# aux-io.net
KiCad netlist of a schematic drawn in EAGLE
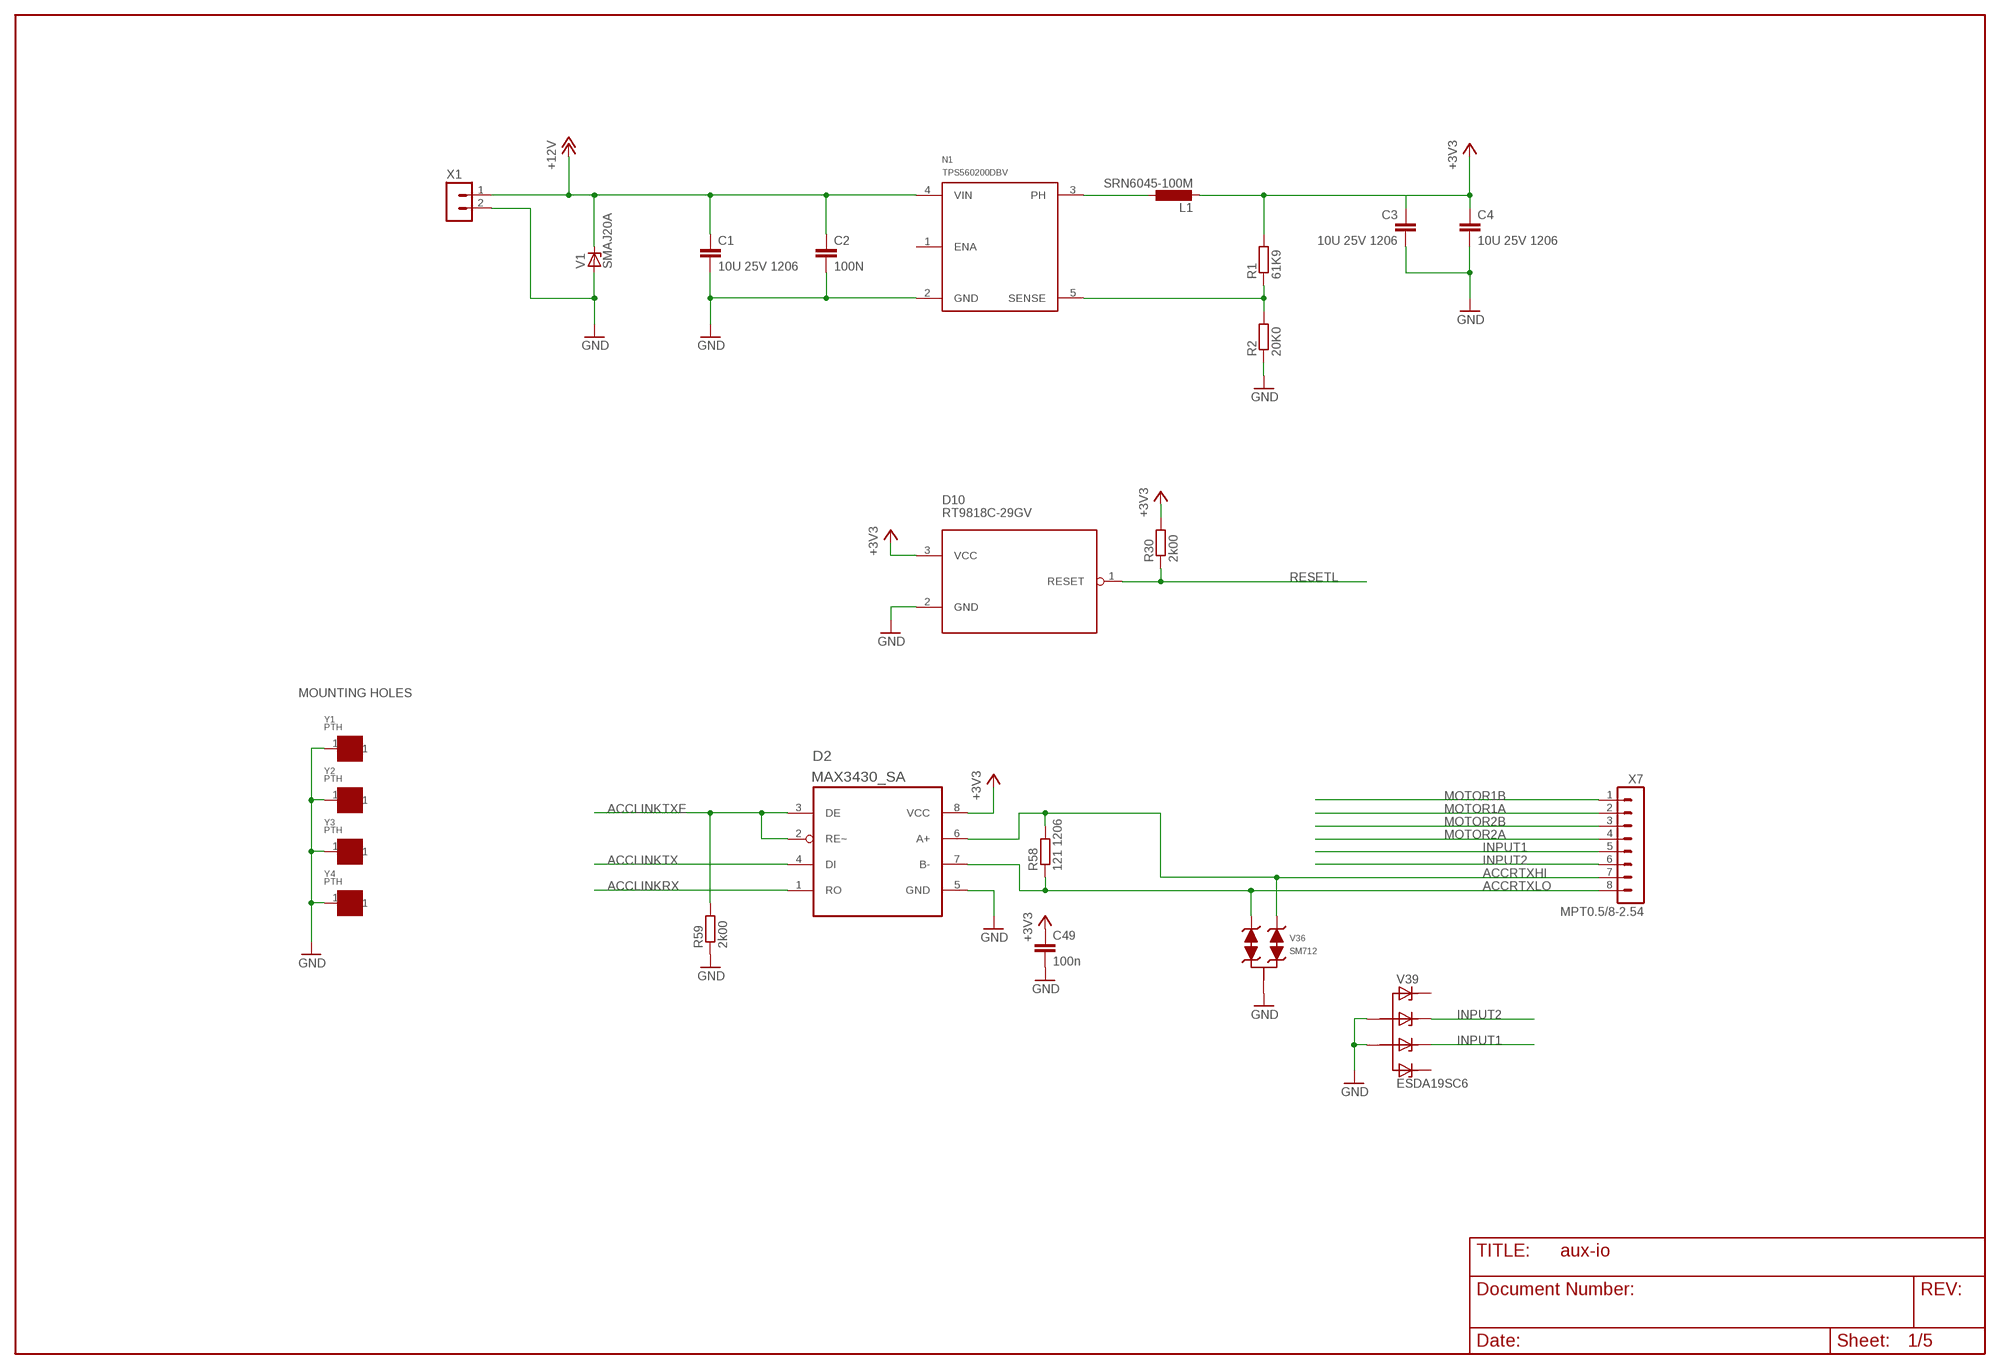
[diagram p0: schematic, sheet 1]
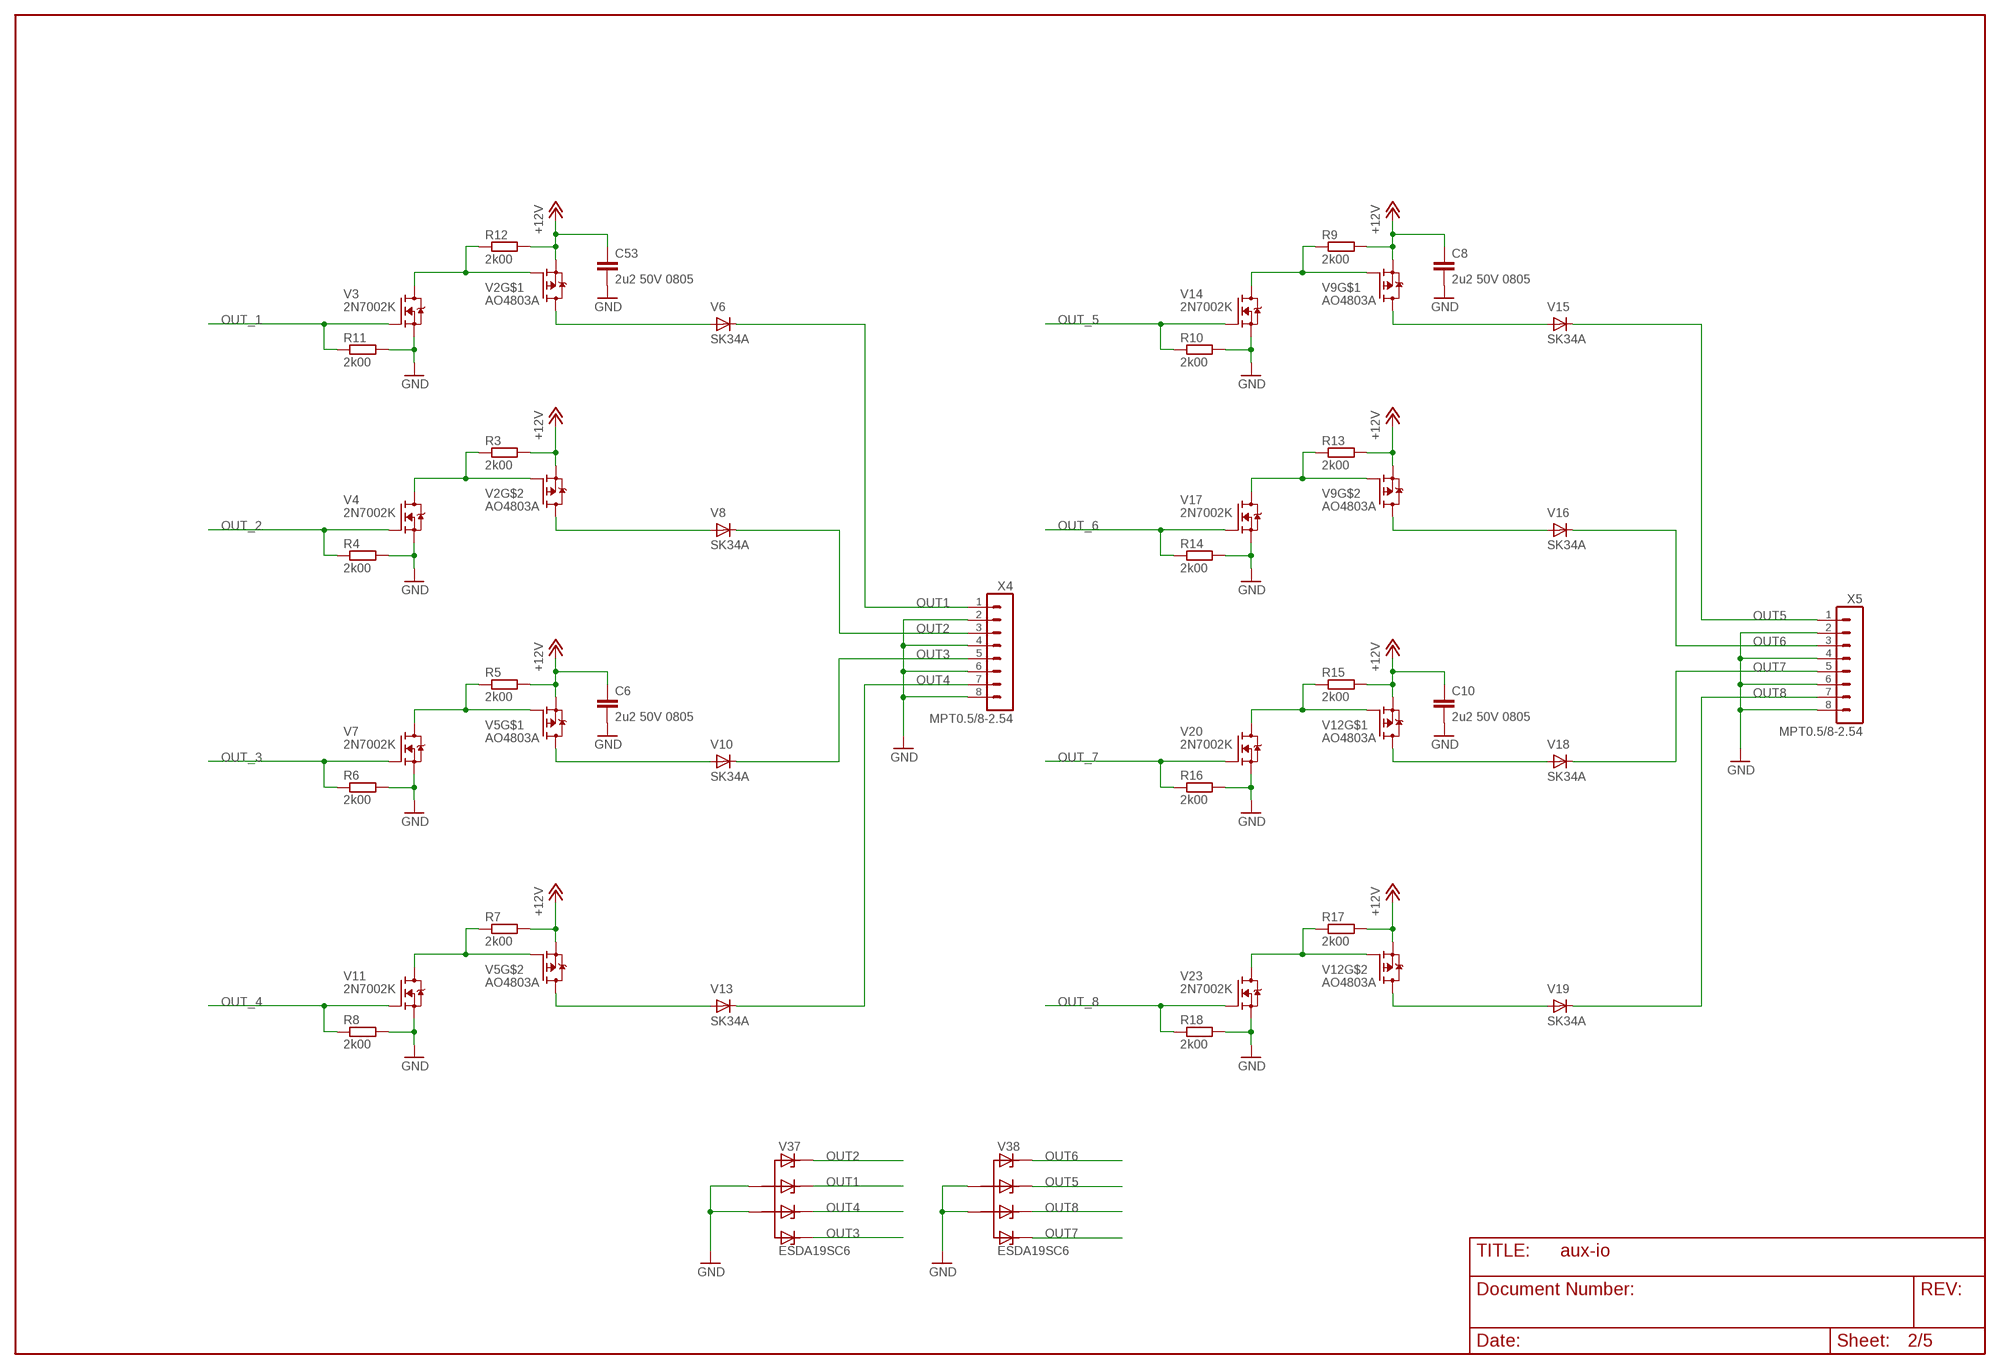
[diagram p1: schematic, sheet 2]
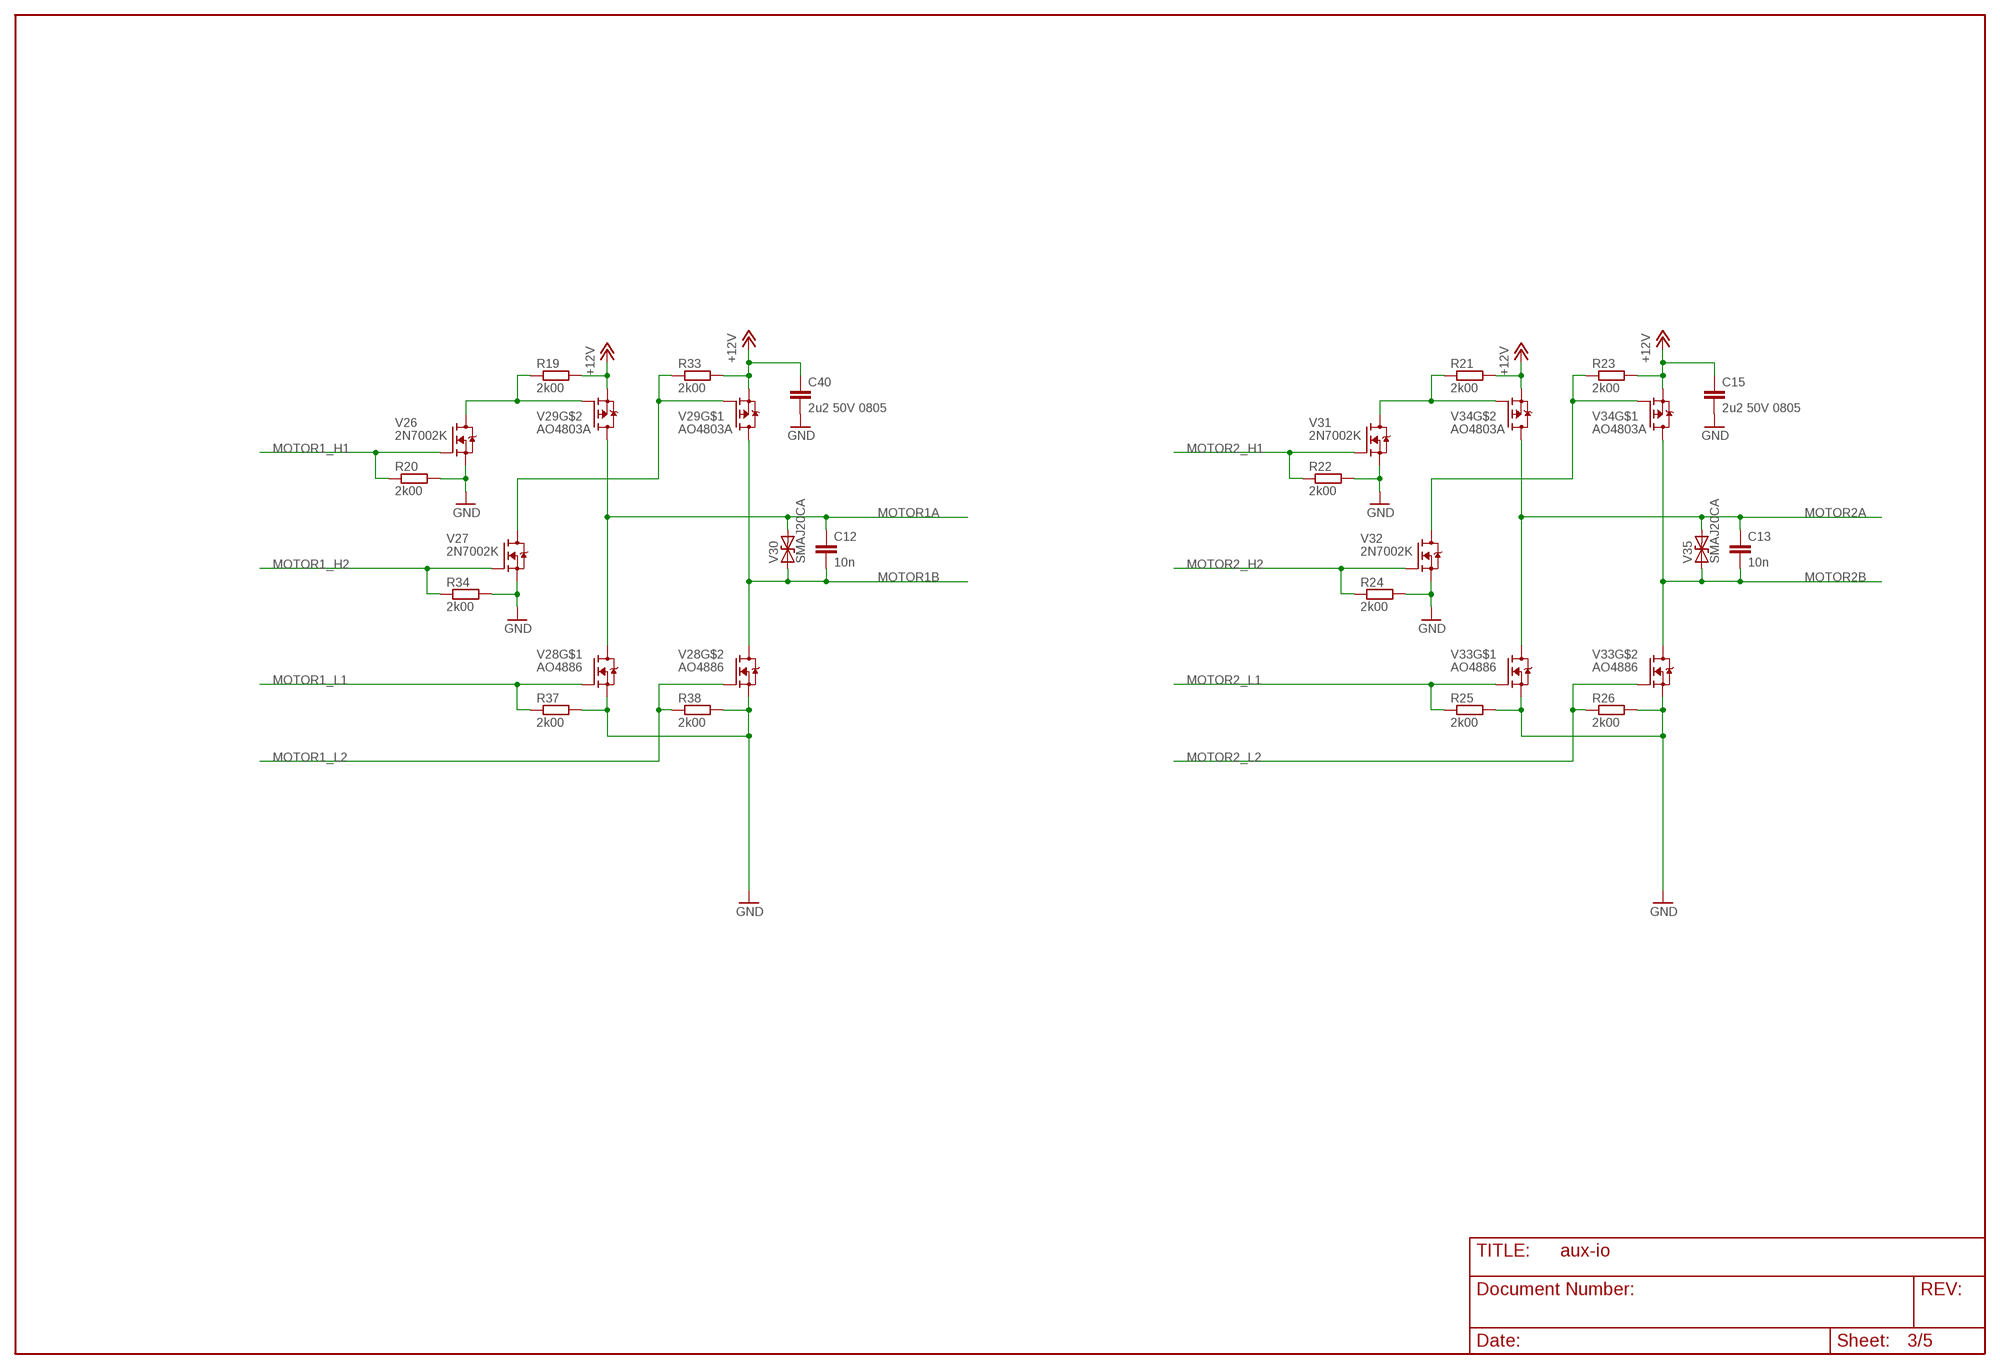
[diagram p2: schematic, sheet 3]
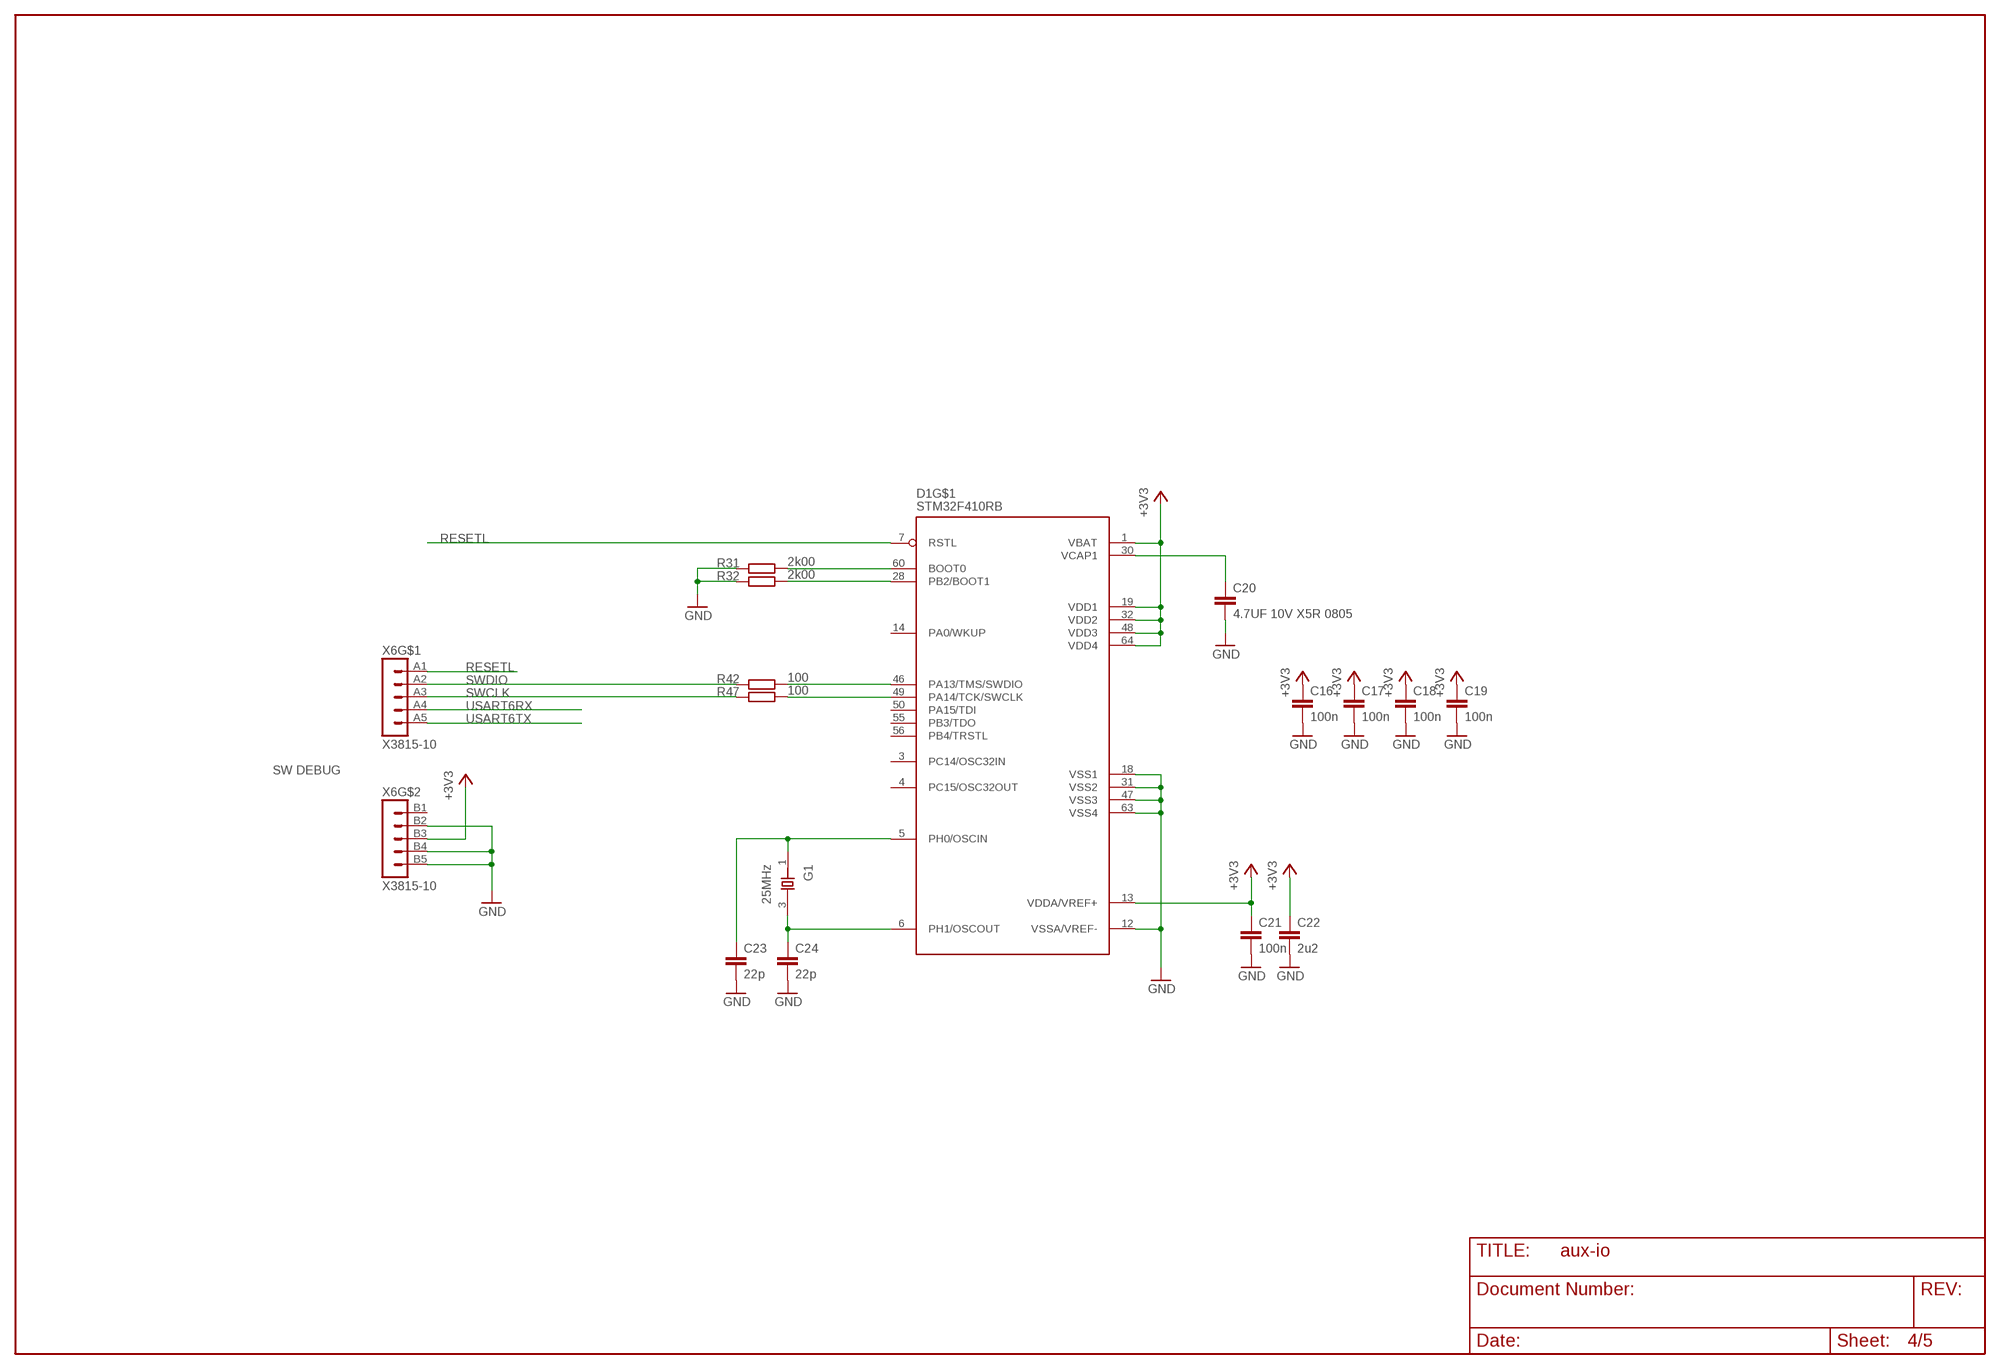
[diagram p3: schematic, sheet 4]
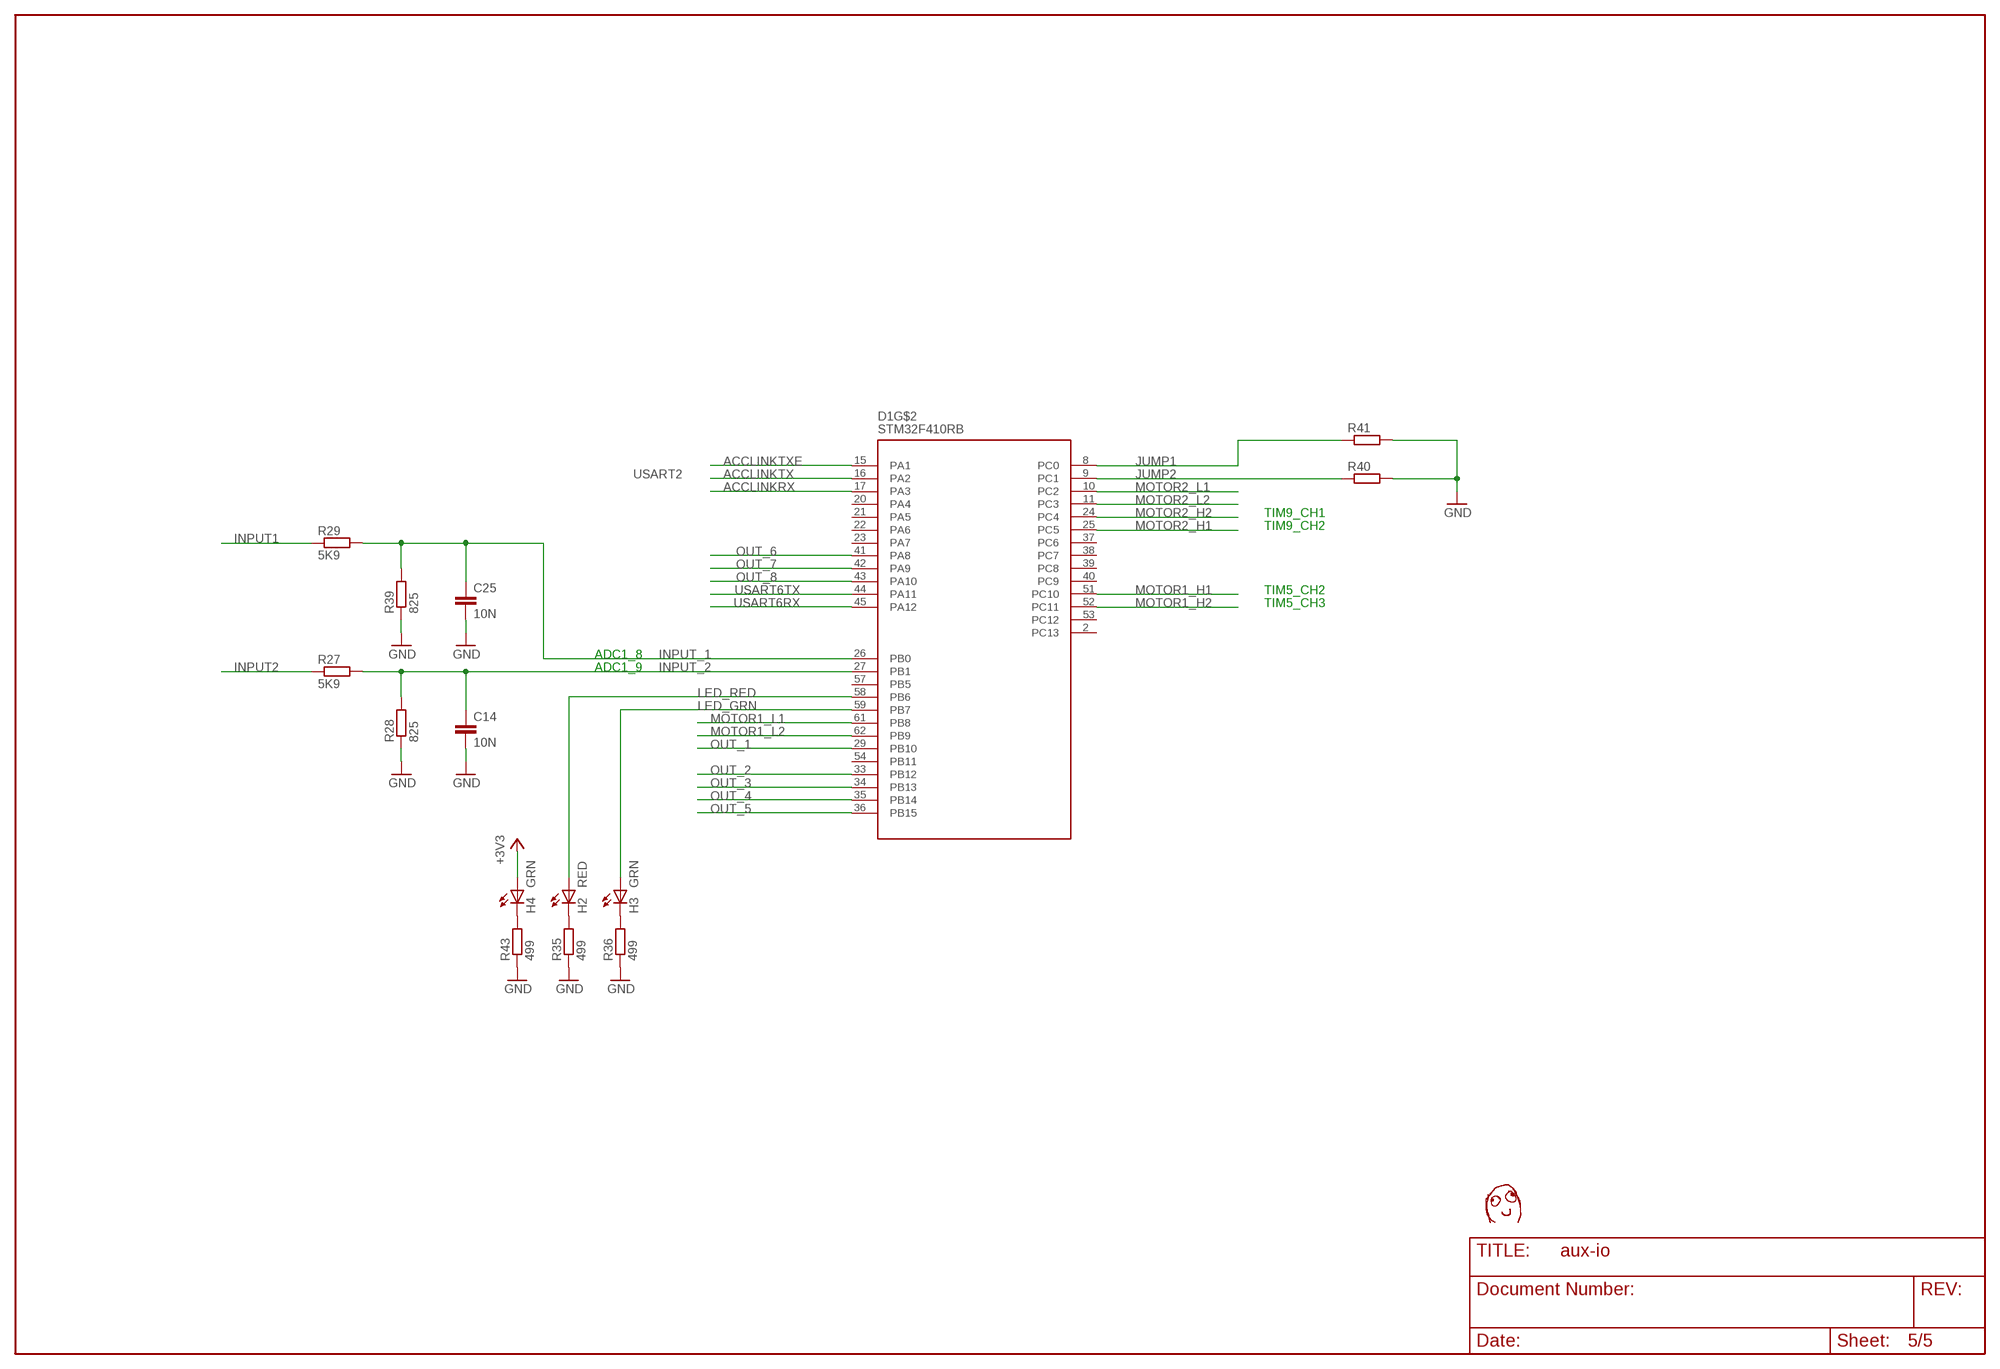
[diagram p4: schematic, sheet 5]

(export (version "E")
  (design (tool "Eeschema 10.0.6"))
  (components
    (comp (ref "C6")
      (value "2u2 50V 0805")
      (footprint "eagle-import:C0805")
      (libsource (lib "eagle-import") (part "CAP0805"))
    )
    (comp (ref "C8")
      (value "2u2 50V 0805")
      (footprint "eagle-import:C0805")
      (libsource (lib "eagle-import") (part "CAP0805"))
    )
    (comp (ref "C10")
      (value "2u2 50V 0805")
      (footprint "eagle-import:C0805")
      (libsource (lib "eagle-import") (part "CAP0805"))
    )
    (comp (ref "C53")
      (value "2u2 50V 0805")
      (footprint "eagle-import:C0805")
      (libsource (lib "eagle-import") (part "CAP0805"))
    )
    (comp (ref "R3")
      (value "2k00")
      (footprint "eagle-import:R0603")
      (libsource (lib "eagle-import") (part "RES0603"))
    )
    (comp (ref "R4")
      (value "2k00")
      (footprint "eagle-import:R0603")
      (libsource (lib "eagle-import") (part "RES0603"))
    )
    (comp (ref "R5")
      (value "2k00")
      (footprint "eagle-import:R0603")
      (libsource (lib "eagle-import") (part "RES0603"))
    )
    (comp (ref "R6")
      (value "2k00")
      (footprint "eagle-import:R0603")
      (libsource (lib "eagle-import") (part "RES0603"))
    )
    (comp (ref "R7")
      (value "2k00")
      (footprint "eagle-import:R0603")
      (libsource (lib "eagle-import") (part "RES0603"))
    )
    (comp (ref "R8")
      (value "2k00")
      (footprint "eagle-import:R0603")
      (libsource (lib "eagle-import") (part "RES0603"))
    )
    (comp (ref "R9")
      (value "2k00")
      (footprint "eagle-import:R0603")
      (libsource (lib "eagle-import") (part "RES0603"))
    )
    (comp (ref "R10")
      (value "2k00")
      (footprint "eagle-import:R0603")
      (libsource (lib "eagle-import") (part "RES0603"))
    )
    (comp (ref "R11")
      (value "2k00")
      (footprint "eagle-import:R0603")
      (libsource (lib "eagle-import") (part "RES0603"))
    )
    (comp (ref "R12")
      (value "2k00")
      (footprint "eagle-import:R0603")
      (libsource (lib "eagle-import") (part "RES0603"))
    )
    (comp (ref "R13")
      (value "2k00")
      (footprint "eagle-import:R0603")
      (libsource (lib "eagle-import") (part "RES0603"))
    )
    (comp (ref "R14")
      (value "2k00")
      (footprint "eagle-import:R0603")
      (libsource (lib "eagle-import") (part "RES0603"))
    )
    (comp (ref "R15")
      (value "2k00")
      (footprint "eagle-import:R0603")
      (libsource (lib "eagle-import") (part "RES0603"))
    )
    (comp (ref "R16")
      (value "2k00")
      (footprint "eagle-import:R0603")
      (libsource (lib "eagle-import") (part "RES0603"))
    )
    (comp (ref "R17")
      (value "2k00")
      (footprint "eagle-import:R0603")
      (libsource (lib "eagle-import") (part "RES0603"))
    )
    (comp (ref "R18")
      (value "2k00")
      (footprint "eagle-import:R0603")
      (libsource (lib "eagle-import") (part "RES0603"))
    )
    (comp (ref "V2")
      (value "AO4803A")
      (footprint "eagle-import:SOIC8-N_MC")
      (libsource (lib "eagle-import") (part "AO4803A"))
    )
    (comp (ref "V3")
      (value "2N7002K")
      (footprint "eagle-import:SOT23")
      (libsource (lib "eagle-import") (part "2N7002K"))
    )
    (comp (ref "V4")
      (value "2N7002K")
      (footprint "eagle-import:SOT23")
      (libsource (lib "eagle-import") (part "2N7002K"))
    )
    (comp (ref "V5")
      (value "AO4803A")
      (footprint "eagle-import:SOIC8-N_MC")
      (libsource (lib "eagle-import") (part "AO4803A"))
    )
    (comp (ref "V6")
      (value "SK34A")
      (footprint "eagle-import:DO214AC")
      (libsource (lib "eagle-import") (part "SK34A"))
    )
    (comp (ref "V7")
      (value "2N7002K")
      (footprint "eagle-import:SOT23")
      (libsource (lib "eagle-import") (part "2N7002K"))
    )
    (comp (ref "V8")
      (value "SK34A")
      (footprint "eagle-import:DO214AC")
      (libsource (lib "eagle-import") (part "SK34A"))
    )
    (comp (ref "V9")
      (value "AO4803A")
      (footprint "eagle-import:SOIC8-N_MC")
      (libsource (lib "eagle-import") (part "AO4803A"))
    )
    (comp (ref "V10")
      (value "SK34A")
      (footprint "eagle-import:DO214AC")
      (libsource (lib "eagle-import") (part "SK34A"))
    )
    (comp (ref "V11")
      (value "2N7002K")
      (footprint "eagle-import:SOT23")
      (libsource (lib "eagle-import") (part "2N7002K"))
    )
    (comp (ref "V12")
      (value "AO4803A")
      (footprint "eagle-import:SOIC8-N_MC")
      (libsource (lib "eagle-import") (part "AO4803A"))
    )
    (comp (ref "V13")
      (value "SK34A")
      (footprint "eagle-import:DO214AC")
      (libsource (lib "eagle-import") (part "SK34A"))
    )
    (comp (ref "V14")
      (value "2N7002K")
      (footprint "eagle-import:SOT23")
      (libsource (lib "eagle-import") (part "2N7002K"))
    )
    (comp (ref "V15")
      (value "SK34A")
      (footprint "eagle-import:DO214AC")
      (libsource (lib "eagle-import") (part "SK34A"))
    )
    (comp (ref "V16")
      (value "SK34A")
      (footprint "eagle-import:DO214AC")
      (libsource (lib "eagle-import") (part "SK34A"))
    )
    (comp (ref "V17")
      (value "2N7002K")
      (footprint "eagle-import:SOT23")
      (libsource (lib "eagle-import") (part "2N7002K"))
    )
    (comp (ref "V18")
      (value "SK34A")
      (footprint "eagle-import:DO214AC")
      (libsource (lib "eagle-import") (part "SK34A"))
    )
    (comp (ref "V19")
      (value "SK34A")
      (footprint "eagle-import:DO214AC")
      (libsource (lib "eagle-import") (part "SK34A"))
    )
    (comp (ref "V20")
      (value "2N7002K")
      (footprint "eagle-import:SOT23")
      (libsource (lib "eagle-import") (part "2N7002K"))
    )
    (comp (ref "V23")
      (value "2N7002K")
      (footprint "eagle-import:SOT23")
      (libsource (lib "eagle-import") (part "2N7002K"))
    )
    (comp (ref "V37")
      (value "ESDA19SC6")
      (footprint "eagle-import:SOT23-6")
      (libsource (lib "eagle-import") (part "ESDAXXSC6"))
    )
    (comp (ref "V38")
      (value "ESDA19SC6")
      (footprint "eagle-import:SOT23-6")
      (libsource (lib "eagle-import") (part "ESDAXXSC6"))
    )
    (comp (ref "X4")
      (value "MPT0.5/8-2.54")
      (footprint "eagle-import:MPT0.5_8-2.54")
      (libsource (lib "eagle-import") (part "MPT0.5/8-2.54"))
    )
    (comp (ref "X5")
      (value "MPT0.5/8-2.54")
      (footprint "eagle-import:MPT0.5_8-2.54")
      (libsource (lib "eagle-import") (part "MPT0.5/8-2.54"))
    )
    (comp (ref "C12")
      (value "10n")
      (footprint "eagle-import:C0603")
      (libsource (lib "eagle-import") (part "CAP0603"))
    )
    (comp (ref "C13")
      (value "10n")
      (footprint "eagle-import:C0603")
      (libsource (lib "eagle-import") (part "CAP0603"))
    )
    (comp (ref "C15")
      (value "2u2 50V 0805")
      (footprint "eagle-import:C0805")
      (libsource (lib "eagle-import") (part "CAP0805"))
    )
    (comp (ref "C40")
      (value "2u2 50V 0805")
      (footprint "eagle-import:C0805")
      (libsource (lib "eagle-import") (part "CAP0805"))
    )
    (comp (ref "R19")
      (value "2k00")
      (footprint "eagle-import:R0603")
      (libsource (lib "eagle-import") (part "RES0603"))
    )
    (comp (ref "R20")
      (value "2k00")
      (footprint "eagle-import:R0603")
      (libsource (lib "eagle-import") (part "RES0603"))
    )
    (comp (ref "R21")
      (value "2k00")
      (footprint "eagle-import:R0603")
      (libsource (lib "eagle-import") (part "RES0603"))
    )
    (comp (ref "R22")
      (value "2k00")
      (footprint "eagle-import:R0603")
      (libsource (lib "eagle-import") (part "RES0603"))
    )
    (comp (ref "R23")
      (value "2k00")
      (footprint "eagle-import:R0603")
      (libsource (lib "eagle-import") (part "RES0603"))
    )
    (comp (ref "R24")
      (value "2k00")
      (footprint "eagle-import:R0603")
      (libsource (lib "eagle-import") (part "RES0603"))
    )
    (comp (ref "R25")
      (value "2k00")
      (footprint "eagle-import:R0603")
      (libsource (lib "eagle-import") (part "RES0603"))
    )
    (comp (ref "R26")
      (value "2k00")
      (footprint "eagle-import:R0603")
      (libsource (lib "eagle-import") (part "RES0603"))
    )
    (comp (ref "R33")
      (value "2k00")
      (footprint "eagle-import:R0603")
      (libsource (lib "eagle-import") (part "RES0603"))
    )
    (comp (ref "R34")
      (value "2k00")
      (footprint "eagle-import:R0603")
      (libsource (lib "eagle-import") (part "RES0603"))
    )
    (comp (ref "R37")
      (value "2k00")
      (footprint "eagle-import:R0603")
      (libsource (lib "eagle-import") (part "RES0603"))
    )
    (comp (ref "R38")
      (value "2k00")
      (footprint "eagle-import:R0603")
      (libsource (lib "eagle-import") (part "RES0603"))
    )
    (comp (ref "V26")
      (value "2N7002K")
      (footprint "eagle-import:SOT23")
      (libsource (lib "eagle-import") (part "2N7002K"))
    )
    (comp (ref "V27")
      (value "2N7002K")
      (footprint "eagle-import:SOT23")
      (libsource (lib "eagle-import") (part "2N7002K"))
    )
    (comp (ref "V28")
      (value "AO4886")
      (footprint "eagle-import:SOIC8-N_MC")
      (libsource (lib "eagle-import") (part "AO4886"))
    )
    (comp (ref "V29")
      (value "AO4803A")
      (footprint "eagle-import:SOIC8-N_MC")
      (libsource (lib "eagle-import") (part "omat_ic_2_AO4803A"))
    )
    (comp (ref "V30")
      (value "SMAJ20CA")
      (footprint "eagle-import:DO214AC")
      (libsource (lib "eagle-import") (part "SMAJXXCA"))
    )
    (comp (ref "V31")
      (value "2N7002K")
      (footprint "eagle-import:SOT23")
      (libsource (lib "eagle-import") (part "2N7002K"))
    )
    (comp (ref "V32")
      (value "2N7002K")
      (footprint "eagle-import:SOT23")
      (libsource (lib "eagle-import") (part "2N7002K"))
    )
    (comp (ref "V33")
      (value "AO4886")
      (footprint "eagle-import:SOIC8-N_MC")
      (libsource (lib "eagle-import") (part "AO4886"))
    )
    (comp (ref "V34")
      (value "AO4803A")
      (footprint "eagle-import:SOIC8-N_MC")
      (libsource (lib "eagle-import") (part "omat_ic_2_AO4803A"))
    )
    (comp (ref "V35")
      (value "SMAJ20CA")
      (footprint "eagle-import:DO214AC")
      (libsource (lib "eagle-import") (part "SMAJXXCA"))
    )
    (comp (ref "C1")
      (value "10U 25V 1206")
      (footprint "eagle-import:C1206")
      (libsource (lib "eagle-import") (part "passiivit_CAP1206"))
    )
    (comp (ref "C2")
      (value "100N")
      (footprint "eagle-import:C0603")
      (libsource (lib "eagle-import") (part "passiivit_CAP0603"))
    )
    (comp (ref "C3")
      (value "10U 25V 1206")
      (footprint "eagle-import:C1206")
      (libsource (lib "eagle-import") (part "passiivit_CAP1206"))
    )
    (comp (ref "C4")
      (value "10U 25V 1206")
      (footprint "eagle-import:C1206")
      (libsource (lib "eagle-import") (part "passiivit_CAP1206"))
    )
    (comp (ref "C49")
      (value "100n")
      (footprint "eagle-import:C0603")
      (libsource (lib "eagle-import") (part "CAP0603"))
    )
    (comp (ref "D2")
      (value "MAX3430_SA")
      (footprint "eagle-import:SOIC8-N_MC")
      (libsource (lib "eagle-import") (part "MAX3088_SA"))
    )
    (comp (ref "D10")
      (value "RT9818C-29GV")
      (footprint "eagle-import:SOT23")
      (libsource (lib "eagle-import") (part "RT9818C-29GV"))
    )
    (comp (ref "L1")
      (value "SRN6045-100M")
      (footprint "eagle-import:SRN6045")
      (libsource (lib "eagle-import") (part "SRN6045-100M"))
    )
    (comp (ref "N1")
      (value "TPS560200DBV")
      (footprint "eagle-import:SOT95P280X145-5N")
      (libsource (lib "eagle-import") (part "TPS560200DBV"))
    )
    (comp (ref "R1")
      (value "61K9")
      (footprint "eagle-import:R0603")
      (libsource (lib "eagle-import") (part "passiivit_RES0603"))
    )
    (comp (ref "R2")
      (value "20K0")
      (footprint "eagle-import:R0603")
      (libsource (lib "eagle-import") (part "passiivit_RES0603"))
    )
    (comp (ref "R30")
      (value "2k00")
      (footprint "eagle-import:R0603")
      (libsource (lib "eagle-import") (part "RES0603"))
    )
    (comp (ref "R58")
      (value "121 1206")
      (footprint "eagle-import:R1206")
      (libsource (lib "eagle-import") (part "RES1206"))
    )
    (comp (ref "R59")
      (value "2k00")
      (footprint "eagle-import:R0603")
      (libsource (lib "eagle-import") (part "RES0603"))
    )
    (comp (ref "V1")
      (value "SMAJ20A")
      (footprint "eagle-import:DO214AC")
      (libsource (lib "eagle-import") (part "SMAJXXA"))
    )
    (comp (ref "V36")
      (value "SM712")
      (footprint "eagle-import:SOT23")
      (libsource (lib "eagle-import") (part "SM712"))
    )
    (comp (ref "V39")
      (value "ESDA19SC6")
      (footprint "eagle-import:SOT23-6")
      (libsource (lib "eagle-import") (part "ESDAXXSC6"))
    )
    (comp (ref "X1")
      (value "TE_RUUVILIITIN2")
      (footprint "eagle-import:TE_RUUVILIITIN2")
      (libsource (lib "eagle-import") (part "TE_RUUVILIITIN2"))
    )
    (comp (ref "X7")
      (value "MPT0.5/8-2.54")
      (footprint "eagle-import:MPT0.5_8-2.54")
      (libsource (lib "eagle-import") (part "MPT0.5/8-2.54"))
    )
    (comp (ref "Y1")
      (value "PTH")
      (footprint "eagle-import:PTH-3.2-6DIA")
      (libsource (lib "eagle-import") (part "PTH"))
    )
    (comp (ref "Y2")
      (value "PTH")
      (footprint "eagle-import:PTH-3.2-6DIA")
      (libsource (lib "eagle-import") (part "PTH"))
    )
    (comp (ref "Y3")
      (value "PTH")
      (footprint "eagle-import:PTH-3.2-6DIA")
      (libsource (lib "eagle-import") (part "PTH"))
    )
    (comp (ref "Y4")
      (value "PTH")
      (footprint "eagle-import:PTH-3.2-6DIA")
      (libsource (lib "eagle-import") (part "PTH"))
    )
    (comp (ref "C16")
      (value "100n")
      (footprint "eagle-import:C0603")
      (libsource (lib "eagle-import") (part "CAP0603"))
    )
    (comp (ref "C17")
      (value "100n")
      (footprint "eagle-import:C0603")
      (libsource (lib "eagle-import") (part "CAP0603"))
    )
    (comp (ref "C18")
      (value "100n")
      (footprint "eagle-import:C0603")
      (libsource (lib "eagle-import") (part "CAP0603"))
    )
    (comp (ref "C19")
      (value "100n")
      (footprint "eagle-import:C0603")
      (libsource (lib "eagle-import") (part "CAP0603"))
    )
    (comp (ref "C20")
      (value "4.7UF 10V X5R 0805")
      (footprint "eagle-import:C0805")
      (libsource (lib "eagle-import") (part "CAP0805"))
    )
    (comp (ref "C21")
      (value "100n")
      (footprint "eagle-import:C0603")
      (libsource (lib "eagle-import") (part "CAP0603"))
    )
    (comp (ref "C22")
      (value "2u2")
      (footprint "eagle-import:C0603")
      (libsource (lib "eagle-import") (part "CAP0603"))
    )
    (comp (ref "C23")
      (value "22p")
      (footprint "eagle-import:C0603")
      (libsource (lib "eagle-import") (part "CAP0603"))
    )
    (comp (ref "C24")
      (value "22p")
      (footprint "eagle-import:C0603")
      (libsource (lib "eagle-import") (part "CAP0603"))
    )
    (comp (ref "D1")
      (value "STM32F410RB")
      (footprint "eagle-import:LQFP-64")
      (libsource (lib "eagle-import") (part "STM32F410RB"))
    )
    (comp (ref "G1")
      (value "25MHz")
      (footprint "eagle-import:X_3225")
      (libsource (lib "eagle-import") (part "XTAL_3225_SMD"))
    )
    (comp (ref "R31")
      (value "2k00")
      (footprint "eagle-import:R0603")
      (libsource (lib "eagle-import") (part "RES0603"))
    )
    (comp (ref "R32")
      (value "2k00")
      (footprint "eagle-import:R0603")
      (libsource (lib "eagle-import") (part "RES0603"))
    )
    (comp (ref "R42")
      (value "100")
      (footprint "eagle-import:R0603")
      (libsource (lib "eagle-import") (part "RES0603"))
    )
    (comp (ref "R47")
      (value "100")
      (footprint "eagle-import:R0603")
      (libsource (lib "eagle-import") (part "RES0603"))
    )
    (comp (ref "X6")
      (value "X3815-10")
      (footprint "eagle-import:15110102601")
      (libsource (lib "eagle-import") (part "X3815-10"))
    )
    (comp (ref "C14")
      (value "10N")
      (footprint "eagle-import:C0603")
      (libsource (lib "eagle-import") (part "passiivit_CAP0603"))
    )
    (comp (ref "C25")
      (value "10N")
      (footprint "eagle-import:C0603")
      (libsource (lib "eagle-import") (part "passiivit_CAP0603"))
    )
    (comp (ref "H2")
      (value "RED")
      (footprint "eagle-import:CHIP-LED0603")
      (libsource (lib "eagle-import") (part "LEDCHIP-LED0603"))
    )
    (comp (ref "H3")
      (value "GRN")
      (footprint "eagle-import:CHIP-LED0603")
      (libsource (lib "eagle-import") (part "LEDCHIP-LED0603"))
    )
    (comp (ref "H4")
      (value "GRN")
      (footprint "eagle-import:CHIP-LED0603")
      (libsource (lib "eagle-import") (part "LEDCHIP-LED0603"))
    )
    (comp (ref "R27")
      (value "5K9")
      (footprint "eagle-import:R1206")
      (libsource (lib "eagle-import") (part "passiivit_RES1206"))
    )
    (comp (ref "R28")
      (value "825")
      (footprint "eagle-import:R0603")
      (libsource (lib "eagle-import") (part "passiivit_RES0603"))
    )
    (comp (ref "R29")
      (value "5K9")
      (footprint "eagle-import:R1206")
      (libsource (lib "eagle-import") (part "passiivit_RES1206"))
    )
    (comp (ref "R35")
      (value "499")
      (footprint "eagle-import:R0603")
      (libsource (lib "eagle-import") (part "RES0603"))
    )
    (comp (ref "R36")
      (value "499")
      (footprint "eagle-import:R0603")
      (libsource (lib "eagle-import") (part "RES0603"))
    )
    (comp (ref "R39")
      (value "825")
      (footprint "eagle-import:R0603")
      (libsource (lib "eagle-import") (part "passiivit_RES0603"))
    )
    (comp (ref "R40")
      (value "RES0603")
      (footprint "eagle-import:R0603")
      (libsource (lib "eagle-import") (part "passiivit_RES0603"))
    )
    (comp (ref "R41")
      (value "RES0603")
      (footprint "eagle-import:R0603")
      (libsource (lib "eagle-import") (part "passiivit_RES0603"))
    )
    (comp (ref "R43")
      (value "499")
      (footprint "eagle-import:R0603")
      (libsource (lib "eagle-import") (part "RES0603"))
    )
    (comp (ref "U$1")
      (value "DAFUG")
      (footprint "eagle-import:DAFUG")
      (libsource (lib "eagle-import") (part "DAFUG"))
    )
  )
  (nets
    (net (code "1") (name "+3V3") (class "Default")
      (node (ref "C16") (pin "1") (pinfunction "1_1") (pintype "passive"))
      (node (ref "C17") (pin "1") (pinfunction "1_1") (pintype "passive"))
      (node (ref "C18") (pin "1") (pinfunction "1_1") (pintype "passive"))
      (node (ref "C19") (pin "1") (pinfunction "1_1") (pintype "passive"))
      (node (ref "C21") (pin "1") (pinfunction "1_1") (pintype "passive"))
      (node (ref "C22") (pin "1") (pinfunction "1_1") (pintype "passive"))
      (node (ref "C3") (pin "1") (pinfunction "1_1") (pintype "passive"))
      (node (ref "C4") (pin "1") (pinfunction "1_1") (pintype "passive"))
      (node (ref "C49") (pin "1") (pinfunction "1_1") (pintype "passive"))
      (node (ref "D1") (pin "1") (pinfunction "VBAT_1") (pintype "bidirectional"))
      (node (ref "D1") (pin "13") (pinfunction "VDDA/VREF+_13") (pintype "bidirectional"))
      (node (ref "D1") (pin "19") (pinfunction "VDD1_19") (pintype "bidirectional"))
      (node (ref "D1") (pin "32") (pinfunction "VDD2_32") (pintype "bidirectional"))
      (node (ref "D1") (pin "48") (pinfunction "VDD3_48") (pintype "bidirectional"))
      (node (ref "D1") (pin "64") (pinfunction "VDD4_64") (pintype "bidirectional"))
      (node (ref "D10") (pin "3") (pinfunction "VCC_3") (pintype "bidirectional"))
      (node (ref "D2") (pin "8") (pinfunction "VCC_8") (pintype "power_in"))
      (node (ref "H4") (pin "A") (pinfunction "A_A") (pintype "passive"))
      (node (ref "L1") (pin "2") (pinfunction "2_2") (pintype "passive"))
      (node (ref "R1") (pin "2") (pinfunction "2_2") (pintype "passive"))
      (node (ref "R30") (pin "2") (pinfunction "2_2") (pintype "passive"))
      (node (ref "X6") (pin "B3") (pinfunction "3_B3") (pintype "passive"))
    )
    (net (code "2") (name "+12V") (class "Default")
      (node (ref "C1") (pin "1") (pinfunction "1_1") (pintype "passive"))
      (node (ref "C10") (pin "1") (pinfunction "1_1") (pintype "passive"))
      (node (ref "C15") (pin "1") (pinfunction "1_1") (pintype "passive"))
      (node (ref "C2") (pin "1") (pinfunction "1_1") (pintype "passive"))
      (node (ref "C40") (pin "1") (pinfunction "1_1") (pintype "passive"))
      (node (ref "C53") (pin "1") (pinfunction "1_1") (pintype "passive"))
      (node (ref "C6") (pin "1") (pinfunction "1_1") (pintype "passive"))
      (node (ref "C8") (pin "1") (pinfunction "1_1") (pintype "passive"))
      (node (ref "N1") (pin "4") (pinfunction "VIN_4") (pintype "bidirectional"))
      (node (ref "R12") (pin "2") (pinfunction "2_2") (pintype "passive"))
      (node (ref "R13") (pin "2") (pinfunction "2_2") (pintype "passive"))
      (node (ref "R15") (pin "2") (pinfunction "2_2") (pintype "passive"))
      (node (ref "R17") (pin "2") (pinfunction "2_2") (pintype "passive"))
      (node (ref "R19") (pin "2") (pinfunction "2_2") (pintype "passive"))
      (node (ref "R21") (pin "2") (pinfunction "2_2") (pintype "passive"))
      (node (ref "R23") (pin "2") (pinfunction "2_2") (pintype "passive"))
      (node (ref "R3") (pin "2") (pinfunction "2_2") (pintype "passive"))
      (node (ref "R33") (pin "2") (pinfunction "2_2") (pintype "passive"))
      (node (ref "R5") (pin "2") (pinfunction "2_2") (pintype "passive"))
      (node (ref "R7") (pin "2") (pinfunction "2_2") (pintype "passive"))
      (node (ref "R9") (pin "2") (pinfunction "2_2") (pintype "passive"))
      (node (ref "V1") (pin "C") (pinfunction "C_C") (pintype "passive"))
      (node (ref "V12") (pin "1") (pinfunction "S_1") (pintype "passive"))
      (node (ref "V12") (pin "3") (pinfunction "S_3") (pintype "passive"))
      (node (ref "V2") (pin "1") (pinfunction "S_1") (pintype "passive"))
      (node (ref "V2") (pin "3") (pinfunction "S_3") (pintype "passive"))
      (node (ref "V29") (pin "1") (pinfunction "S_1") (pintype "passive"))
      (node (ref "V29") (pin "3") (pinfunction "S_3") (pintype "passive"))
      (node (ref "V34") (pin "1") (pinfunction "S_1") (pintype "passive"))
      (node (ref "V34") (pin "3") (pinfunction "S_3") (pintype "passive"))
      (node (ref "V5") (pin "1") (pinfunction "S_1") (pintype "passive"))
      (node (ref "V5") (pin "3") (pinfunction "S_3") (pintype "passive"))
      (node (ref "V9") (pin "1") (pinfunction "S_1") (pintype "passive"))
      (node (ref "V9") (pin "3") (pinfunction "S_3") (pintype "passive"))
      (node (ref "X1") (pin "1") (pinfunction "1_1") (pintype "passive"))
    )
    (net (code "3") (name "ACCLINKRX") (class "Default")
      (node (ref "D1") (pin "17") (pinfunction "PA3_17") (pintype "bidirectional"))
      (node (ref "D2") (pin "1") (pinfunction "RO_1") (pintype "output"))
    )
    (net (code "4") (name "ACCLINKTX") (class "Default")
      (node (ref "D1") (pin "16") (pinfunction "PA2_16") (pintype "bidirectional"))
      (node (ref "D2") (pin "4") (pinfunction "DI_4") (pintype "input"))
    )
    (net (code "5") (name "ACCLINKTXE") (class "Default")
      (node (ref "D1") (pin "15") (pinfunction "PA1_15") (pintype "bidirectional"))
      (node (ref "D2") (pin "2") (pinfunction "RE~{}_2") (pintype "input"))
      (node (ref "D2") (pin "3") (pinfunction "DE_3") (pintype "input"))
      (node (ref "R59") (pin "2") (pinfunction "2_2") (pintype "passive"))
    )
    (net (code "6") (name "ACCRTXHI") (class "Default")
      (node (ref "D2") (pin "6") (pinfunction "A+_6") (pintype "bidirectional"))
      (node (ref "R58") (pin "2") (pinfunction "2_2") (pintype "passive"))
      (node (ref "V36") (pin "1") (pinfunction "1_1") (pintype "bidirectional"))
      (node (ref "X7") (pin "7") (pinfunction "7_7") (pintype "passive"))
    )
    (net (code "7") (name "ACCRTXLO") (class "Default")
      (node (ref "D2") (pin "7") (pinfunction "B-_7") (pintype "bidirectional"))
      (node (ref "R58") (pin "1") (pinfunction "1_1") (pintype "passive"))
      (node (ref "V36") (pin "2") (pinfunction "2_2") (pintype "bidirectional"))
      (node (ref "X7") (pin "8") (pinfunction "8_8") (pintype "passive"))
    )
    (net (code "8") (name "GND") (class "Default")
      (node (ref "C1") (pin "2") (pinfunction "2_2") (pintype "passive"))
      (node (ref "C10") (pin "2") (pinfunction "2_2") (pintype "passive"))
      (node (ref "C14") (pin "2") (pinfunction "2_2") (pintype "passive"))
      (node (ref "C15") (pin "2") (pinfunction "2_2") (pintype "passive"))
      (node (ref "C16") (pin "2") (pinfunction "2_2") (pintype "passive"))
      (node (ref "C17") (pin "2") (pinfunction "2_2") (pintype "passive"))
      (node (ref "C18") (pin "2") (pinfunction "2_2") (pintype "passive"))
      (node (ref "C19") (pin "2") (pinfunction "2_2") (pintype "passive"))
      (node (ref "C2") (pin "2") (pinfunction "2_2") (pintype "passive"))
      (node (ref "C20") (pin "2") (pinfunction "2_2") (pintype "passive"))
      (node (ref "C21") (pin "2") (pinfunction "2_2") (pintype "passive"))
      (node (ref "C22") (pin "2") (pinfunction "2_2") (pintype "passive"))
      (node (ref "C23") (pin "2") (pinfunction "2_2") (pintype "passive"))
      (node (ref "C24") (pin "2") (pinfunction "2_2") (pintype "passive"))
      (node (ref "C25") (pin "2") (pinfunction "2_2") (pintype "passive"))
      (node (ref "C3") (pin "2") (pinfunction "2_2") (pintype "passive"))
      (node (ref "C4") (pin "2") (pinfunction "2_2") (pintype "passive"))
      (node (ref "C40") (pin "2") (pinfunction "2_2") (pintype "passive"))
      (node (ref "C49") (pin "2") (pinfunction "2_2") (pintype "passive"))
      (node (ref "C53") (pin "2") (pinfunction "2_2") (pintype "passive"))
      (node (ref "C6") (pin "2") (pinfunction "2_2") (pintype "passive"))
      (node (ref "C8") (pin "2") (pinfunction "2_2") (pintype "passive"))
      (node (ref "D1") (pin "12") (pinfunction "VSSA/VREF-_12") (pintype "bidirectional"))
      (node (ref "D1") (pin "18") (pinfunction "VSS1_18") (pintype "bidirectional"))
      (node (ref "D1") (pin "31") (pinfunction "VSS2_31") (pintype "bidirectional"))
      (node (ref "D1") (pin "47") (pinfunction "VSS3_47") (pintype "bidirectional"))
      (node (ref "D1") (pin "63") (pinfunction "VSS4_63") (pintype "bidirectional"))
      (node (ref "D10") (pin "2") (pinfunction "GND_2") (pintype "bidirectional"))
      (node (ref "D2") (pin "5") (pinfunction "GND_5") (pintype "power_in"))
      (node (ref "N1") (pin "2") (pinfunction "GND_2") (pintype "bidirectional"))
      (node (ref "R10") (pin "2") (pinfunction "2_2") (pintype "passive"))
      (node (ref "R11") (pin "2") (pinfunction "2_2") (pintype "passive"))
      (node (ref "R14") (pin "2") (pinfunction "2_2") (pintype "passive"))
      (node (ref "R16") (pin "2") (pinfunction "2_2") (pintype "passive"))
      (node (ref "R18") (pin "2") (pinfunction "2_2") (pintype "passive"))
      (node (ref "R2") (pin "1") (pinfunction "1_1") (pintype "passive"))
      (node (ref "R20") (pin "2") (pinfunction "2_2") (pintype "passive"))
      (node (ref "R22") (pin "2") (pinfunction "2_2") (pintype "passive"))
      (node (ref "R24") (pin "2") (pinfunction "2_2") (pintype "passive"))
      (node (ref "R25") (pin "2") (pinfunction "2_2") (pintype "passive"))
      (node (ref "R26") (pin "2") (pinfunction "2_2") (pintype "passive"))
      (node (ref "R28") (pin "1") (pinfunction "1_1") (pintype "passive"))
      (node (ref "R31") (pin "1") (pinfunction "1_1") (pintype "passive"))
      (node (ref "R32") (pin "1") (pinfunction "1_1") (pintype "passive"))
      (node (ref "R34") (pin "2") (pinfunction "2_2") (pintype "passive"))
      (node (ref "R35") (pin "1") (pinfunction "1_1") (pintype "passive"))
      (node (ref "R36") (pin "1") (pinfunction "1_1") (pintype "passive"))
      (node (ref "R37") (pin "2") (pinfunction "2_2") (pintype "passive"))
      (node (ref "R38") (pin "2") (pinfunction "2_2") (pintype "passive"))
      (node (ref "R39") (pin "1") (pinfunction "1_1") (pintype "passive"))
      (node (ref "R4") (pin "2") (pinfunction "2_2") (pintype "passive"))
      (node (ref "R40") (pin "2") (pinfunction "2_2") (pintype "passive"))
      (node (ref "R41") (pin "2") (pinfunction "2_2") (pintype "passive"))
      (node (ref "R43") (pin "1") (pinfunction "1_1") (pintype "passive"))
      (node (ref "R59") (pin "1") (pinfunction "1_1") (pintype "passive"))
      (node (ref "R6") (pin "2") (pinfunction "2_2") (pintype "passive"))
      (node (ref "R8") (pin "2") (pinfunction "2_2") (pintype "passive"))
      (node (ref "V1") (pin "A") (pinfunction "A_A") (pintype "passive"))
      (node (ref "V11") (pin "2") (pinfunction "S_2") (pintype "passive"))
      (node (ref "V14") (pin "2") (pinfunction "S_2") (pintype "passive"))
      (node (ref "V17") (pin "2") (pinfunction "S_2") (pintype "passive"))
      (node (ref "V20") (pin "2") (pinfunction "S_2") (pintype "passive"))
      (node (ref "V23") (pin "2") (pinfunction "S_2") (pintype "passive"))
      (node (ref "V26") (pin "2") (pinfunction "S_2") (pintype "passive"))
      (node (ref "V27") (pin "2") (pinfunction "S_2") (pintype "passive"))
      (node (ref "V28") (pin "1") (pinfunction "S_1") (pintype "passive"))
      (node (ref "V28") (pin "3") (pinfunction "S_3") (pintype "passive"))
      (node (ref "V3") (pin "2") (pinfunction "S_2") (pintype "passive"))
      (node (ref "V31") (pin "2") (pinfunction "S_2") (pintype "passive"))
      (node (ref "V32") (pin "2") (pinfunction "S_2") (pintype "passive"))
      (node (ref "V33") (pin "1") (pinfunction "S_1") (pintype "passive"))
      (node (ref "V33") (pin "3") (pinfunction "S_3") (pintype "passive"))
      (node (ref "V36") (pin "3") (pinfunction "3_3") (pintype "bidirectional"))
      (node (ref "V37") (pin "2") (pinfunction "A_2") (pintype "passive"))
      (node (ref "V37") (pin "5") (pinfunction "A1_5") (pintype "passive"))
      (node (ref "V38") (pin "2") (pinfunction "A_2") (pintype "passive"))
      (node (ref "V38") (pin "5") (pinfunction "A1_5") (pintype "passive"))
      (node (ref "V39") (pin "2") (pinfunction "A_2") (pintype "passive"))
      (node (ref "V39") (pin "5") (pinfunction "A1_5") (pintype "passive"))
      (node (ref "V4") (pin "2") (pinfunction "S_2") (pintype "passive"))
      (node (ref "V7") (pin "2") (pinfunction "S_2") (pintype "passive"))
      (node (ref "X1") (pin "2") (pinfunction "2_2") (pintype "passive"))
      (node (ref "X4") (pin "2") (pinfunction "2_2") (pintype "passive"))
      (node (ref "X4") (pin "4") (pinfunction "4_4") (pintype "passive"))
      (node (ref "X4") (pin "6") (pinfunction "6_6") (pintype "passive"))
      (node (ref "X4") (pin "8") (pinfunction "8_8") (pintype "passive"))
      (node (ref "X5") (pin "2") (pinfunction "2_2") (pintype "passive"))
      (node (ref "X5") (pin "4") (pinfunction "4_4") (pintype "passive"))
      (node (ref "X5") (pin "6") (pinfunction "6_6") (pintype "passive"))
      (node (ref "X5") (pin "8") (pinfunction "8_8") (pintype "passive"))
      (node (ref "X6") (pin "B2") (pinfunction "2_B2") (pintype "passive"))
      (node (ref "X6") (pin "B4") (pinfunction "4_B4") (pintype "passive"))
      (node (ref "X6") (pin "B5") (pinfunction "5_B5") (pintype "passive"))
      (node (ref "Y1") (pin "1") (pinfunction "1_1") (pintype "bidirectional"))
      (node (ref "Y2") (pin "1") (pinfunction "1_1") (pintype "bidirectional"))
      (node (ref "Y3") (pin "1") (pinfunction "1_1") (pintype "bidirectional"))
      (node (ref "Y4") (pin "1") (pinfunction "1_1") (pintype "bidirectional"))
    )
    (net (code "9") (name "INPUT1") (class "Default")
      (node (ref "R29") (pin "1") (pinfunction "1_1") (pintype "passive"))
      (node (ref "V39") (pin "4") (pinfunction "C2_4") (pintype "passive"))
      (node (ref "X7") (pin "5") (pinfunction "5_5") (pintype "passive"))
    )
    (net (code "10") (name "INPUT2") (class "Default")
      (node (ref "R27") (pin "1") (pinfunction "1_1") (pintype "passive"))
      (node (ref "V39") (pin "3") (pinfunction "C1_3") (pintype "passive"))
      (node (ref "X7") (pin "6") (pinfunction "6_6") (pintype "passive"))
    )
    (net (code "11") (name "INPUT_1") (class "Default")
      (node (ref "C25") (pin "1") (pinfunction "1_1") (pintype "passive"))
      (node (ref "D1") (pin "26") (pinfunction "PB0_26") (pintype "bidirectional"))
      (node (ref "R29") (pin "2") (pinfunction "2_2") (pintype "passive"))
      (node (ref "R39") (pin "2") (pinfunction "2_2") (pintype "passive"))
    )
    (net (code "12") (name "INPUT_2") (class "Default")
      (node (ref "C14") (pin "1") (pinfunction "1_1") (pintype "passive"))
      (node (ref "D1") (pin "27") (pinfunction "PB1_27") (pintype "bidirectional"))
      (node (ref "R27") (pin "2") (pinfunction "2_2") (pintype "passive"))
      (node (ref "R28") (pin "2") (pinfunction "2_2") (pintype "passive"))
    )
    (net (code "13") (name "JUMP1") (class "Default")
      (node (ref "D1") (pin "8") (pinfunction "PC0_8") (pintype "bidirectional"))
      (node (ref "R41") (pin "1") (pinfunction "1_1") (pintype "passive"))
    )
    (net (code "14") (name "JUMP2") (class "Default")
      (node (ref "D1") (pin "9") (pinfunction "PC1_9") (pintype "bidirectional"))
      (node (ref "R40") (pin "1") (pinfunction "1_1") (pintype "passive"))
    )
    (net (code "15") (name "LED_GRN") (class "Default")
      (node (ref "D1") (pin "59") (pinfunction "PB7_59") (pintype "bidirectional"))
      (node (ref "H3") (pin "A") (pinfunction "A_A") (pintype "passive"))
    )
    (net (code "16") (name "LED_RED") (class "Default")
      (node (ref "D1") (pin "58") (pinfunction "PB6_58") (pintype "bidirectional"))
      (node (ref "H2") (pin "A") (pinfunction "A_A") (pintype "passive"))
    )
    (net (code "17") (name "MOTOR1A") (class "Default")
      (node (ref "C12") (pin "1") (pinfunction "1_1") (pintype "passive"))
      (node (ref "V28") (pin "5") (pinfunction "D_5") (pintype "passive"))
      (node (ref "V28") (pin "6") (pinfunction "D_6") (pintype "passive"))
      (node (ref "V29") (pin "7") (pinfunction "D_7") (pintype "passive"))
      (node (ref "V29") (pin "8") (pinfunction "D_8") (pintype "passive"))
      (node (ref "V30") (pin "A") (pinfunction "2_A") (pintype "passive"))
      (node (ref "X7") (pin "2") (pinfunction "2_2") (pintype "passive"))
    )
    (net (code "18") (name "MOTOR1B") (class "Default")
      (node (ref "C12") (pin "2") (pinfunction "2_2") (pintype "passive"))
      (node (ref "V28") (pin "7") (pinfunction "D_7") (pintype "passive"))
      (node (ref "V28") (pin "8") (pinfunction "D_8") (pintype "passive"))
      (node (ref "V29") (pin "5") (pinfunction "D_5") (pintype "passive"))
      (node (ref "V29") (pin "6") (pinfunction "D_6") (pintype "passive"))
      (node (ref "V30") (pin "C") (pinfunction "1_C") (pintype "passive"))
      (node (ref "X7") (pin "1") (pinfunction "1_1") (pintype "passive"))
    )
    (net (code "19") (name "MOTOR1_H1") (class "Default")
      (node (ref "D1") (pin "51") (pinfunction "PC10_51") (pintype "bidirectional"))
      (node (ref "R20") (pin "1") (pinfunction "1_1") (pintype "passive"))
      (node (ref "V26") (pin "1") (pinfunction "G_1") (pintype "passive"))
    )
    (net (code "20") (name "MOTOR1_H2") (class "Default")
      (node (ref "D1") (pin "52") (pinfunction "PC11_52") (pintype "bidirectional"))
      (node (ref "R34") (pin "1") (pinfunction "1_1") (pintype "passive"))
      (node (ref "V27") (pin "1") (pinfunction "G_1") (pintype "passive"))
    )
    (net (code "21") (name "MOTOR1_L1") (class "Default")
      (node (ref "D1") (pin "61") (pinfunction "PB8_61") (pintype "bidirectional"))
      (node (ref "R37") (pin "1") (pinfunction "1_1") (pintype "passive"))
      (node (ref "V28") (pin "4") (pinfunction "G_4") (pintype "passive"))
    )
    (net (code "22") (name "MOTOR1_L2") (class "Default")
      (node (ref "D1") (pin "62") (pinfunction "PB9_62") (pintype "bidirectional"))
      (node (ref "R38") (pin "1") (pinfunction "1_1") (pintype "passive"))
      (node (ref "V28") (pin "2") (pinfunction "G_2") (pintype "passive"))
    )
    (net (code "23") (name "MOTOR2A") (class "Default")
      (node (ref "C13") (pin "1") (pinfunction "1_1") (pintype "passive"))
      (node (ref "V33") (pin "5") (pinfunction "D_5") (pintype "passive"))
      (node (ref "V33") (pin "6") (pinfunction "D_6") (pintype "passive"))
      (node (ref "V34") (pin "7") (pinfunction "D_7") (pintype "passive"))
      (node (ref "V34") (pin "8") (pinfunction "D_8") (pintype "passive"))
      (node (ref "V35") (pin "A") (pinfunction "2_A") (pintype "passive"))
      (node (ref "X7") (pin "4") (pinfunction "4_4") (pintype "passive"))
    )
    (net (code "24") (name "MOTOR2B") (class "Default")
      (node (ref "C13") (pin "2") (pinfunction "2_2") (pintype "passive"))
      (node (ref "V33") (pin "7") (pinfunction "D_7") (pintype "passive"))
      (node (ref "V33") (pin "8") (pinfunction "D_8") (pintype "passive"))
      (node (ref "V34") (pin "5") (pinfunction "D_5") (pintype "passive"))
      (node (ref "V34") (pin "6") (pinfunction "D_6") (pintype "passive"))
      (node (ref "V35") (pin "C") (pinfunction "1_C") (pintype "passive"))
      (node (ref "X7") (pin "3") (pinfunction "3_3") (pintype "passive"))
    )
    (net (code "25") (name "MOTOR2_H1") (class "Default")
      (node (ref "D1") (pin "25") (pinfunction "PC5_25") (pintype "bidirectional"))
      (node (ref "R22") (pin "1") (pinfunction "1_1") (pintype "passive"))
      (node (ref "V31") (pin "1") (pinfunction "G_1") (pintype "passive"))
    )
    (net (code "26") (name "MOTOR2_H2") (class "Default")
      (node (ref "D1") (pin "24") (pinfunction "PC4_24") (pintype "bidirectional"))
      (node (ref "R24") (pin "1") (pinfunction "1_1") (pintype "passive"))
      (node (ref "V32") (pin "1") (pinfunction "G_1") (pintype "passive"))
    )
    (net (code "27") (name "MOTOR2_L1") (class "Default")
      (node (ref "D1") (pin "10") (pinfunction "PC2_10") (pintype "bidirectional"))
      (node (ref "R25") (pin "1") (pinfunction "1_1") (pintype "passive"))
      (node (ref "V33") (pin "4") (pinfunction "G_4") (pintype "passive"))
    )
    (net (code "28") (name "MOTOR2_L2") (class "Default")
      (node (ref "D1") (pin "11") (pinfunction "PC3_11") (pintype "bidirectional"))
      (node (ref "R26") (pin "1") (pinfunction "1_1") (pintype "passive"))
      (node (ref "V33") (pin "2") (pinfunction "G_2") (pintype "passive"))
    )
    (net (code "29") (name "Net-(D1A-BOOT0)") (class "Default")
      (node (ref "D1") (pin "60") (pinfunction "BOOT0_60") (pintype "bidirectional"))
      (node (ref "R31") (pin "2") (pinfunction "2_2") (pintype "passive"))
    )
    (net (code "30") (name "Net-(D1A-PA13{slash}TMS{slash}SWDIO)") (class "Default")
      (node (ref "D1") (pin "46") (pinfunction "PA13/TMS/SWDIO_46") (pintype "bidirectional"))
      (node (ref "R42") (pin "2") (pinfunction "2_2") (pintype "passive"))
    )
    (net (code "31") (name "Net-(D1A-PA14{slash}TCK{slash}SWCLK)") (class "Default")
      (node (ref "D1") (pin "49") (pinfunction "PA14/TCK/SWCLK_49") (pintype "bidirectional"))
      (node (ref "R47") (pin "2") (pinfunction "2_2") (pintype "passive"))
    )
    (net (code "32") (name "Net-(D1A-PB2{slash}BOOT1)") (class "Default")
      (node (ref "D1") (pin "28") (pinfunction "PB2/BOOT1_28") (pintype "bidirectional"))
      (node (ref "R32") (pin "2") (pinfunction "2_2") (pintype "passive"))
    )
    (net (code "33") (name "Net-(D1A-PH0{slash}OSCIN)") (class "Default")
      (node (ref "C23") (pin "1") (pinfunction "1_1") (pintype "passive"))
      (node (ref "D1") (pin "5") (pinfunction "PH0/OSCIN_5") (pintype "bidirectional"))
      (node (ref "G1") (pin "1") (pinfunction "X1_1") (pintype "bidirectional"))
    )
    (net (code "34") (name "Net-(D1A-PH1{slash}OSCOUT)") (class "Default")
      (node (ref "C24") (pin "1") (pinfunction "1_1") (pintype "passive"))
      (node (ref "D1") (pin "6") (pinfunction "PH1/OSCOUT_6") (pintype "bidirectional"))
      (node (ref "G1") (pin "3") (pinfunction "X2_3") (pintype "bidirectional"))
    )
    (net (code "35") (name "Net-(D1A-VCAP1)") (class "Default")
      (node (ref "C20") (pin "1") (pinfunction "1_1") (pintype "passive"))
      (node (ref "D1") (pin "30") (pinfunction "VCAP1_30") (pintype "bidirectional"))
    )
    (net (code "36") (name "Net-(H2-PadC)") (class "Default")
      (node (ref "H2") (pin "C") (pinfunction "C_C") (pintype "passive"))
      (node (ref "R35") (pin "2") (pinfunction "2_2") (pintype "passive"))
    )
    (net (code "37") (name "Net-(H3-PadC)") (class "Default")
      (node (ref "H3") (pin "C") (pinfunction "C_C") (pintype "passive"))
      (node (ref "R36") (pin "2") (pinfunction "2_2") (pintype "passive"))
    )
    (net (code "38") (name "Net-(H4-PadC)") (class "Default")
      (node (ref "H4") (pin "C") (pinfunction "C_C") (pintype "passive"))
      (node (ref "R43") (pin "2") (pinfunction "2_2") (pintype "passive"))
    )
    (net (code "39") (name "Net-(N1-PH)") (class "Default")
      (node (ref "L1") (pin "1") (pinfunction "1_1") (pintype "passive"))
      (node (ref "N1") (pin "3") (pinfunction "PH_3") (pintype "bidirectional"))
    )
    (net (code "40") (name "Net-(N1-SENSE)") (class "Default")
      (node (ref "N1") (pin "5") (pinfunction "SENSE_5") (pintype "bidirectional"))
      (node (ref "R1") (pin "1") (pinfunction "1_1") (pintype "passive"))
      (node (ref "R2") (pin "2") (pinfunction "2_2") (pintype "passive"))
    )
    (net (code "41") (name "Net-(V2A-D-Pad5)") (class "Default")
      (node (ref "V2") (pin "5") (pinfunction "D_5") (pintype "passive"))
      (node (ref "V2") (pin "6") (pinfunction "D_6") (pintype "passive"))
      (node (ref "V6") (pin "A") (pinfunction "A_A") (pintype "passive"))
    )
    (net (code "42") (name "Net-(V2A-G)") (class "Default")
      (node (ref "R12") (pin "1") (pinfunction "1_1") (pintype "passive"))
      (node (ref "V2") (pin "4") (pinfunction "G_4") (pintype "passive"))
      (node (ref "V3") (pin "3") (pinfunction "D_3") (pintype "passive"))
    )
    (net (code "43") (name "Net-(V2B-D-Pad7)") (class "Default")
      (node (ref "V2") (pin "7") (pinfunction "D_7") (pintype "passive"))
      (node (ref "V2") (pin "8") (pinfunction "D_8") (pintype "passive"))
      (node (ref "V8") (pin "A") (pinfunction "A_A") (pintype "passive"))
    )
    (net (code "44") (name "Net-(V2B-G)") (class "Default")
      (node (ref "R3") (pin "1") (pinfunction "1_1") (pintype "passive"))
      (node (ref "V2") (pin "2") (pinfunction "G_2") (pintype "passive"))
      (node (ref "V4") (pin "3") (pinfunction "D_3") (pintype "passive"))
    )
    (net (code "45") (name "Net-(V5A-G)") (class "Default")
      (node (ref "R5") (pin "1") (pinfunction "1_1") (pintype "passive"))
      (node (ref "V5") (pin "4") (pinfunction "G_4") (pintype "passive"))
      (node (ref "V7") (pin "3") (pinfunction "D_3") (pintype "passive"))
    )
    (net (code "46") (name "Net-(V10-PadA)") (class "Default")
      (node (ref "V10") (pin "A") (pinfunction "A_A") (pintype "passive"))
      (node (ref "V5") (pin "5") (pinfunction "D_5") (pintype "passive"))
      (node (ref "V5") (pin "6") (pinfunction "D_6") (pintype "passive"))
    )
    (net (code "47") (name "Net-(V11-D)") (class "Default")
      (node (ref "R7") (pin "1") (pinfunction "1_1") (pintype "passive"))
      (node (ref "V11") (pin "3") (pinfunction "D_3") (pintype "passive"))
      (node (ref "V5") (pin "2") (pinfunction "G_2") (pintype "passive"))
    )
    (net (code "48") (name "Net-(V12A-D-Pad5)") (class "Default")
      (node (ref "V12") (pin "5") (pinfunction "D_5") (pintype "passive"))
      (node (ref "V12") (pin "6") (pinfunction "D_6") (pintype "passive"))
      (node (ref "V18") (pin "A") (pinfunction "A_A") (pintype "passive"))
    )
    (net (code "49") (name "Net-(V12A-G)") (class "Default")
      (node (ref "R15") (pin "1") (pinfunction "1_1") (pintype "passive"))
      (node (ref "V12") (pin "4") (pinfunction "G_4") (pintype "passive"))
      (node (ref "V20") (pin "3") (pinfunction "D_3") (pintype "passive"))
    )
    (net (code "50") (name "Net-(V12B-D-Pad7)") (class "Default")
      (node (ref "V12") (pin "7") (pinfunction "D_7") (pintype "passive"))
      (node (ref "V12") (pin "8") (pinfunction "D_8") (pintype "passive"))
      (node (ref "V19") (pin "A") (pinfunction "A_A") (pintype "passive"))
    )
    (net (code "51") (name "Net-(V12B-G)") (class "Default")
      (node (ref "R17") (pin "1") (pinfunction "1_1") (pintype "passive"))
      (node (ref "V12") (pin "2") (pinfunction "G_2") (pintype "passive"))
      (node (ref "V23") (pin "3") (pinfunction "D_3") (pintype "passive"))
    )
    (net (code "52") (name "Net-(V13-PadA)") (class "Default")
      (node (ref "V13") (pin "A") (pinfunction "A_A") (pintype "passive"))
      (node (ref "V5") (pin "7") (pinfunction "D_7") (pintype "passive"))
      (node (ref "V5") (pin "8") (pinfunction "D_8") (pintype "passive"))
    )
    (net (code "53") (name "Net-(V14-D)") (class "Default")
      (node (ref "R9") (pin "1") (pinfunction "1_1") (pintype "passive"))
      (node (ref "V14") (pin "3") (pinfunction "D_3") (pintype "passive"))
      (node (ref "V9") (pin "4") (pinfunction "G_4") (pintype "passive"))
    )
    (net (code "54") (name "Net-(V15-PadA)") (class "Default")
      (node (ref "V15") (pin "A") (pinfunction "A_A") (pintype "passive"))
      (node (ref "V9") (pin "5") (pinfunction "D_5") (pintype "passive"))
      (node (ref "V9") (pin "6") (pinfunction "D_6") (pintype "passive"))
    )
    (net (code "55") (name "Net-(V16-PadA)") (class "Default")
      (node (ref "V16") (pin "A") (pinfunction "A_A") (pintype "passive"))
      (node (ref "V9") (pin "7") (pinfunction "D_7") (pintype "passive"))
      (node (ref "V9") (pin "8") (pinfunction "D_8") (pintype "passive"))
    )
    (net (code "56") (name "Net-(V17-D)") (class "Default")
      (node (ref "R13") (pin "1") (pinfunction "1_1") (pintype "passive"))
      (node (ref "V17") (pin "3") (pinfunction "D_3") (pintype "passive"))
      (node (ref "V9") (pin "2") (pinfunction "G_2") (pintype "passive"))
    )
    (net (code "57") (name "Net-(V26-D)") (class "Default")
      (node (ref "R19") (pin "1") (pinfunction "1_1") (pintype "passive"))
      (node (ref "V26") (pin "3") (pinfunction "D_3") (pintype "passive"))
      (node (ref "V29") (pin "2") (pinfunction "G_2") (pintype "passive"))
    )
    (net (code "58") (name "Net-(V27-D)") (class "Default")
      (node (ref "R33") (pin "1") (pinfunction "1_1") (pintype "passive"))
      (node (ref "V27") (pin "3") (pinfunction "D_3") (pintype "passive"))
      (node (ref "V29") (pin "4") (pinfunction "G_4") (pintype "passive"))
    )
    (net (code "59") (name "Net-(V31-D)") (class "Default")
      (node (ref "R21") (pin "1") (pinfunction "1_1") (pintype "passive"))
      (node (ref "V31") (pin "3") (pinfunction "D_3") (pintype "passive"))
      (node (ref "V34") (pin "2") (pinfunction "G_2") (pintype "passive"))
    )
    (net (code "60") (name "Net-(V32-D)") (class "Default")
      (node (ref "R23") (pin "1") (pinfunction "1_1") (pintype "passive"))
      (node (ref "V32") (pin "3") (pinfunction "D_3") (pintype "passive"))
      (node (ref "V34") (pin "4") (pinfunction "G_4") (pintype "passive"))
    )
    (net (code "61") (name "OUT1") (class "Default")
      (node (ref "V37") (pin "3") (pinfunction "C1_3") (pintype "passive"))
      (node (ref "V6") (pin "C") (pinfunction "C_C") (pintype "passive"))
      (node (ref "X4") (pin "1") (pinfunction "1_1") (pintype "passive"))
    )
    (net (code "62") (name "OUT2") (class "Default")
      (node (ref "V37") (pin "1") (pinfunction "C_1") (pintype "passive"))
      (node (ref "V8") (pin "C") (pinfunction "C_C") (pintype "passive"))
      (node (ref "X4") (pin "3") (pinfunction "3_3") (pintype "passive"))
    )
    (net (code "63") (name "OUT3") (class "Default")
      (node (ref "V10") (pin "C") (pinfunction "C_C") (pintype "passive"))
      (node (ref "V37") (pin "6") (pinfunction "C3_6") (pintype "passive"))
      (node (ref "X4") (pin "5") (pinfunction "5_5") (pintype "passive"))
    )
    (net (code "64") (name "OUT4") (class "Default")
      (node (ref "V13") (pin "C") (pinfunction "C_C") (pintype "passive"))
      (node (ref "V37") (pin "4") (pinfunction "C2_4") (pintype "passive"))
      (node (ref "X4") (pin "7") (pinfunction "7_7") (pintype "passive"))
    )
    (net (code "65") (name "OUT5") (class "Default")
      (node (ref "V15") (pin "C") (pinfunction "C_C") (pintype "passive"))
      (node (ref "V38") (pin "3") (pinfunction "C1_3") (pintype "passive"))
      (node (ref "X5") (pin "1") (pinfunction "1_1") (pintype "passive"))
    )
    (net (code "66") (name "OUT6") (class "Default")
      (node (ref "V16") (pin "C") (pinfunction "C_C") (pintype "passive"))
      (node (ref "V38") (pin "1") (pinfunction "C_1") (pintype "passive"))
      (node (ref "X5") (pin "3") (pinfunction "3_3") (pintype "passive"))
    )
    (net (code "67") (name "OUT7") (class "Default")
      (node (ref "V18") (pin "C") (pinfunction "C_C") (pintype "passive"))
      (node (ref "V38") (pin "6") (pinfunction "C3_6") (pintype "passive"))
      (node (ref "X5") (pin "5") (pinfunction "5_5") (pintype "passive"))
    )
    (net (code "68") (name "OUT8") (class "Default")
      (node (ref "V19") (pin "C") (pinfunction "C_C") (pintype "passive"))
      (node (ref "V38") (pin "4") (pinfunction "C2_4") (pintype "passive"))
      (node (ref "X5") (pin "7") (pinfunction "7_7") (pintype "passive"))
    )
    (net (code "69") (name "OUT_1") (class "Default")
      (node (ref "D1") (pin "29") (pinfunction "PB10_29") (pintype "bidirectional"))
      (node (ref "R11") (pin "1") (pinfunction "1_1") (pintype "passive"))
      (node (ref "V3") (pin "1") (pinfunction "G_1") (pintype "passive"))
    )
    (net (code "70") (name "OUT_2") (class "Default")
      (node (ref "D1") (pin "33") (pinfunction "PB12_33") (pintype "bidirectional"))
      (node (ref "R4") (pin "1") (pinfunction "1_1") (pintype "passive"))
      (node (ref "V4") (pin "1") (pinfunction "G_1") (pintype "passive"))
    )
    (net (code "71") (name "OUT_3") (class "Default")
      (node (ref "D1") (pin "34") (pinfunction "PB13_34") (pintype "bidirectional"))
      (node (ref "R6") (pin "1") (pinfunction "1_1") (pintype "passive"))
      (node (ref "V7") (pin "1") (pinfunction "G_1") (pintype "passive"))
    )
    (net (code "72") (name "OUT_4") (class "Default")
      (node (ref "D1") (pin "35") (pinfunction "PB14_35") (pintype "bidirectional"))
      (node (ref "R8") (pin "1") (pinfunction "1_1") (pintype "passive"))
      (node (ref "V11") (pin "1") (pinfunction "G_1") (pintype "passive"))
    )
    (net (code "73") (name "OUT_5") (class "Default")
      (node (ref "D1") (pin "36") (pinfunction "PB15_36") (pintype "bidirectional"))
      (node (ref "R10") (pin "1") (pinfunction "1_1") (pintype "passive"))
      (node (ref "V14") (pin "1") (pinfunction "G_1") (pintype "passive"))
    )
    (net (code "74") (name "OUT_6") (class "Default")
      (node (ref "D1") (pin "41") (pinfunction "PA8_41") (pintype "bidirectional"))
      (node (ref "R14") (pin "1") (pinfunction "1_1") (pintype "passive"))
      (node (ref "V17") (pin "1") (pinfunction "G_1") (pintype "passive"))
    )
    (net (code "75") (name "OUT_7") (class "Default")
      (node (ref "D1") (pin "42") (pinfunction "PA9_42") (pintype "bidirectional"))
      (node (ref "R16") (pin "1") (pinfunction "1_1") (pintype "passive"))
      (node (ref "V20") (pin "1") (pinfunction "G_1") (pintype "passive"))
    )
    (net (code "76") (name "OUT_8") (class "Default")
      (node (ref "D1") (pin "43") (pinfunction "PA10_43") (pintype "bidirectional"))
      (node (ref "R18") (pin "1") (pinfunction "1_1") (pintype "passive"))
      (node (ref "V23") (pin "1") (pinfunction "G_1") (pintype "passive"))
    )
    (net (code "77") (name "RESETL") (class "Default")
      (node (ref "D1") (pin "7") (pinfunction "RSTL_7") (pintype "bidirectional"))
      (node (ref "D10") (pin "1") (pinfunction "RESET_1") (pintype "bidirectional"))
      (node (ref "R30") (pin "1") (pinfunction "1_1") (pintype "passive"))
      (node (ref "X6") (pin "A1") (pinfunction "1_A1") (pintype "passive"))
    )
    (net (code "78") (name "SWCLK") (class "Default")
      (node (ref "R47") (pin "1") (pinfunction "1_1") (pintype "passive"))
      (node (ref "X6") (pin "A3") (pinfunction "3_A3") (pintype "passive"))
    )
    (net (code "79") (name "SWDIO") (class "Default")
      (node (ref "R42") (pin "1") (pinfunction "1_1") (pintype "passive"))
      (node (ref "X6") (pin "A2") (pinfunction "2_A2") (pintype "passive"))
    )
    (net (code "80") (name "USART6RX") (class "Default")
      (node (ref "D1") (pin "45") (pinfunction "PA12_45") (pintype "bidirectional"))
      (node (ref "X6") (pin "A4") (pinfunction "4_A4") (pintype "passive"))
    )
    (net (code "81") (name "USART6TX") (class "Default")
      (node (ref "D1") (pin "44") (pinfunction "PA11_44") (pintype "bidirectional"))
      (node (ref "X6") (pin "A5") (pinfunction "5_A5") (pintype "passive"))
    )
    (net (code "82") (name "unconnected-(D1A-PA0{slash}WKUP-Pad14)") (class "Default")
      (node (ref "D1") (pin "14") (pinfunction "PA0/WKUP_14") (pintype "bidirectional"))
    )
    (net (code "83") (name "unconnected-(D1A-PA15{slash}TDI-Pad50)") (class "Default")
      (node (ref "D1") (pin "50") (pinfunction "PA15/TDI_50") (pintype "bidirectional"))
    )
    (net (code "84") (name "unconnected-(D1A-PB3{slash}TDO-Pad55)") (class "Default")
      (node (ref "D1") (pin "55") (pinfunction "PB3/TDO_55") (pintype "bidirectional"))
    )
    (net (code "85") (name "unconnected-(D1A-PB4{slash}TRSTL-Pad56)") (class "Default")
      (node (ref "D1") (pin "56") (pinfunction "PB4/TRSTL_56") (pintype "bidirectional"))
    )
    (net (code "86") (name "unconnected-(D1A-PC14{slash}OSC32IN-Pad3)") (class "Default")
      (node (ref "D1") (pin "3") (pinfunction "PC14/OSC32IN_3") (pintype "bidirectional"))
    )
    (net (code "87") (name "unconnected-(D1A-PC15{slash}OSC32OUT-Pad4)") (class "Default")
      (node (ref "D1") (pin "4") (pinfunction "PC15/OSC32OUT_4") (pintype "bidirectional"))
    )
    (net (code "88") (name "unconnected-(D1B-PA4-Pad20)") (class "Default")
      (node (ref "D1") (pin "20") (pinfunction "PA4_20") (pintype "bidirectional"))
    )
    (net (code "89") (name "unconnected-(D1B-PA5-Pad21)") (class "Default")
      (node (ref "D1") (pin "21") (pinfunction "PA5_21") (pintype "bidirectional"))
    )
    (net (code "90") (name "unconnected-(D1B-PA6-Pad22)") (class "Default")
      (node (ref "D1") (pin "22") (pinfunction "PA6_22") (pintype "bidirectional"))
    )
    (net (code "91") (name "unconnected-(D1B-PA7-Pad23)") (class "Default")
      (node (ref "D1") (pin "23") (pinfunction "PA7_23") (pintype "bidirectional"))
    )
    (net (code "92") (name "unconnected-(D1B-PB5-Pad57)") (class "Default")
      (node (ref "D1") (pin "57") (pinfunction "PB5_57") (pintype "bidirectional"))
    )
    (net (code "93") (name "unconnected-(D1B-PB11-Pad54)") (class "Default")
      (node (ref "D1") (pin "54") (pinfunction "PB11_54") (pintype "bidirectional"))
    )
    (net (code "94") (name "unconnected-(D1B-PC6-Pad37)") (class "Default")
      (node (ref "D1") (pin "37") (pinfunction "PC6_37") (pintype "bidirectional"))
    )
    (net (code "95") (name "unconnected-(D1B-PC7-Pad38)") (class "Default")
      (node (ref "D1") (pin "38") (pinfunction "PC7_38") (pintype "bidirectional"))
    )
    (net (code "96") (name "unconnected-(D1B-PC8-Pad39)") (class "Default")
      (node (ref "D1") (pin "39") (pinfunction "PC8_39") (pintype "bidirectional"))
    )
    (net (code "97") (name "unconnected-(D1B-PC9-Pad40)") (class "Default")
      (node (ref "D1") (pin "40") (pinfunction "PC9_40") (pintype "bidirectional"))
    )
    (net (code "98") (name "unconnected-(D1B-PC12-Pad53)") (class "Default")
      (node (ref "D1") (pin "53") (pinfunction "PC12_53") (pintype "bidirectional"))
    )
    (net (code "99") (name "unconnected-(D1B-PC13-Pad2)") (class "Default")
      (node (ref "D1") (pin "2") (pinfunction "PC13_2") (pintype "bidirectional"))
    )
    (net (code "100") (name "unconnected-(N1-ENA-Pad1)") (class "Default")
      (node (ref "N1") (pin "1") (pinfunction "ENA_1") (pintype "bidirectional"))
    )
    (net (code "101") (name "unconnected-(V39-C-Pad1)") (class "Default")
      (node (ref "V39") (pin "1") (pinfunction "C_1") (pintype "passive"))
    )
    (net (code "102") (name "unconnected-(V39-C3-Pad6)") (class "Default")
      (node (ref "V39") (pin "6") (pinfunction "C3_6") (pintype "passive"))
    )
    (net (code "103") (name "unconnected-(X6B-1-PadB1)") (class "Default")
      (node (ref "X6") (pin "B1") (pinfunction "1_B1") (pintype "passive"))
    )
  )
)
